# EEZ_PSU_power_board_r5B6c.net
KiCad netlist of a schematic drawn in EAGLE
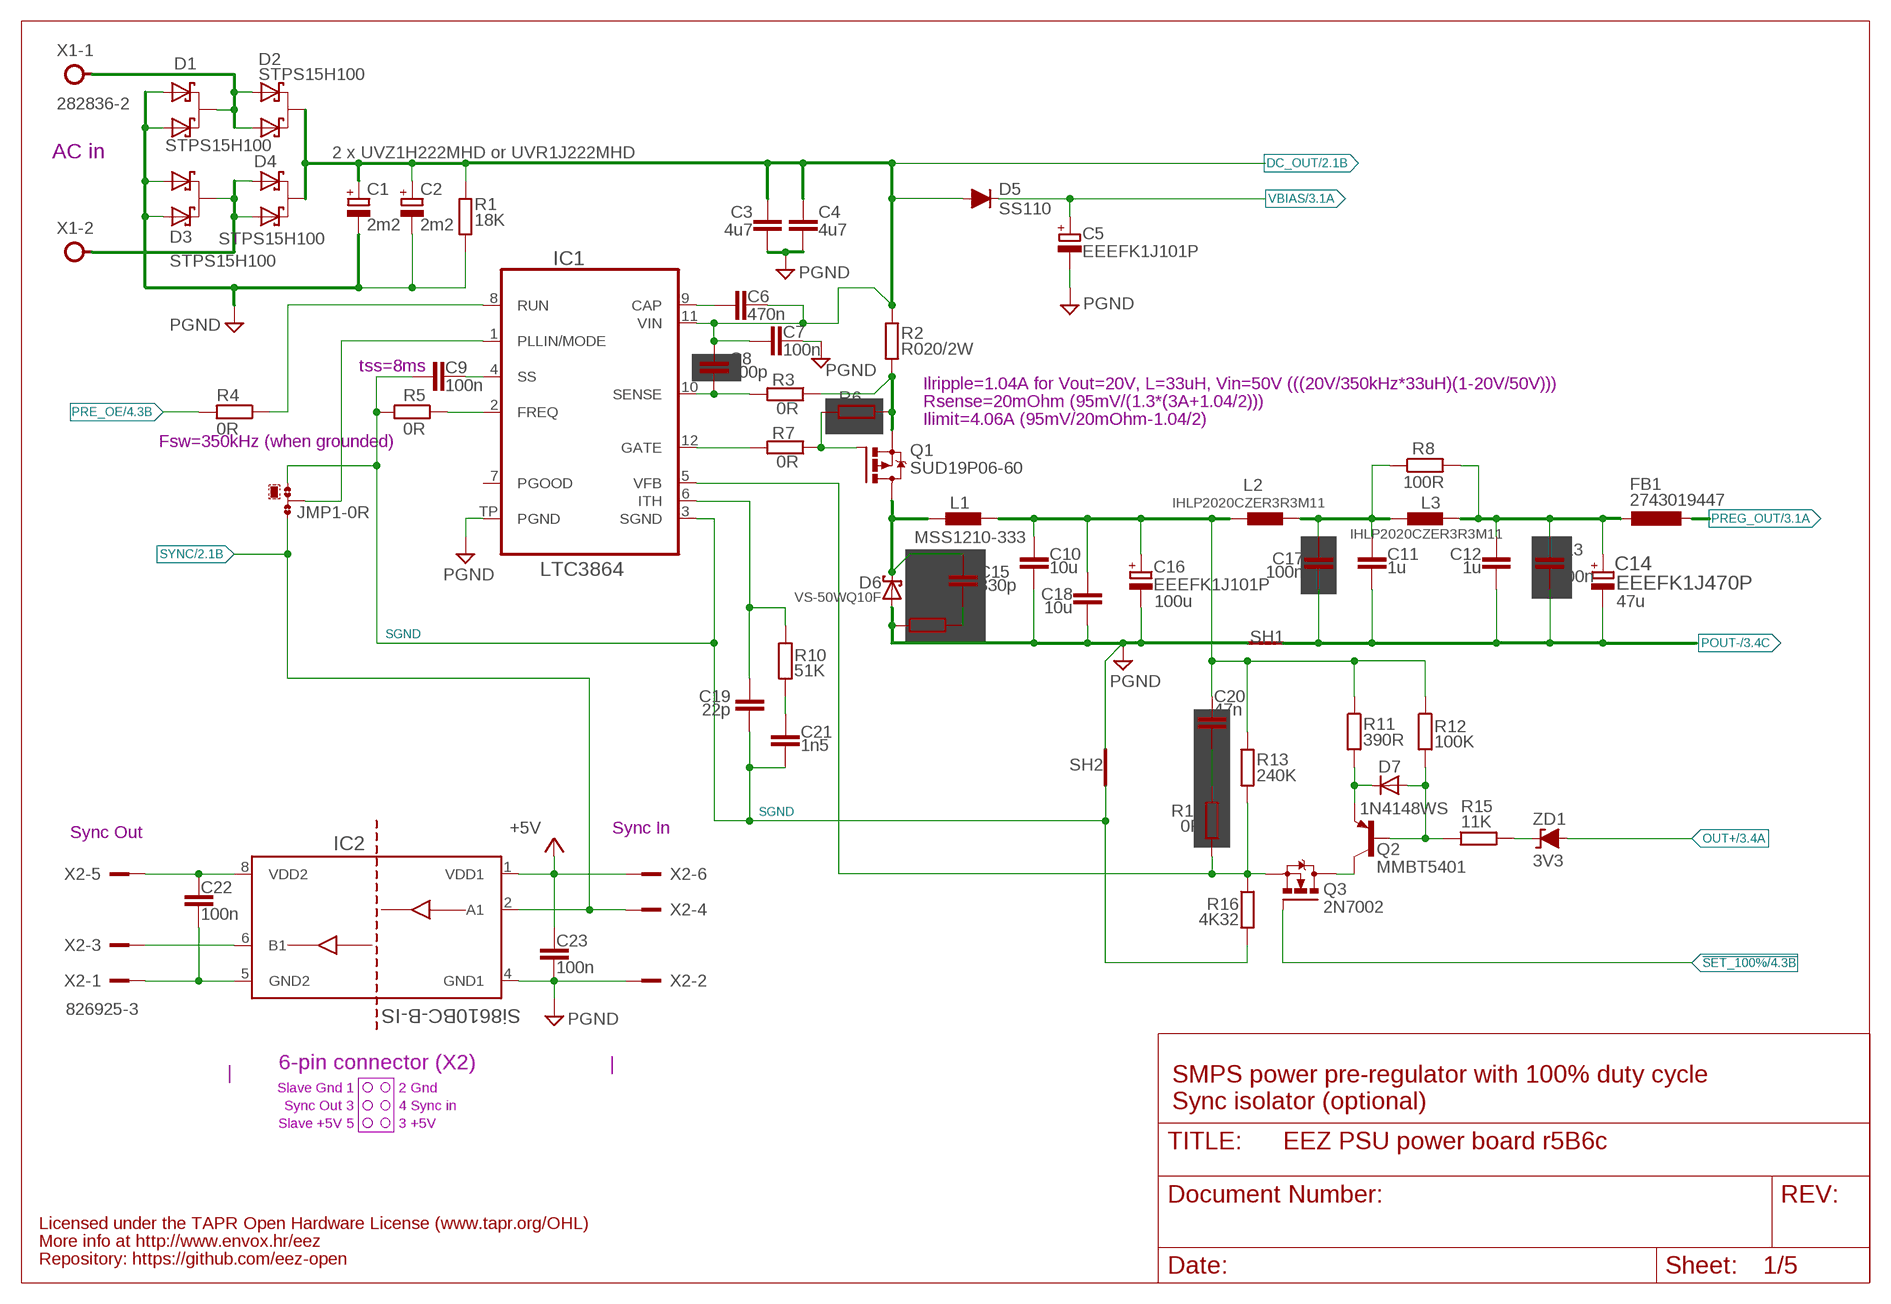
[diagram p0: schematic, sheet 1]
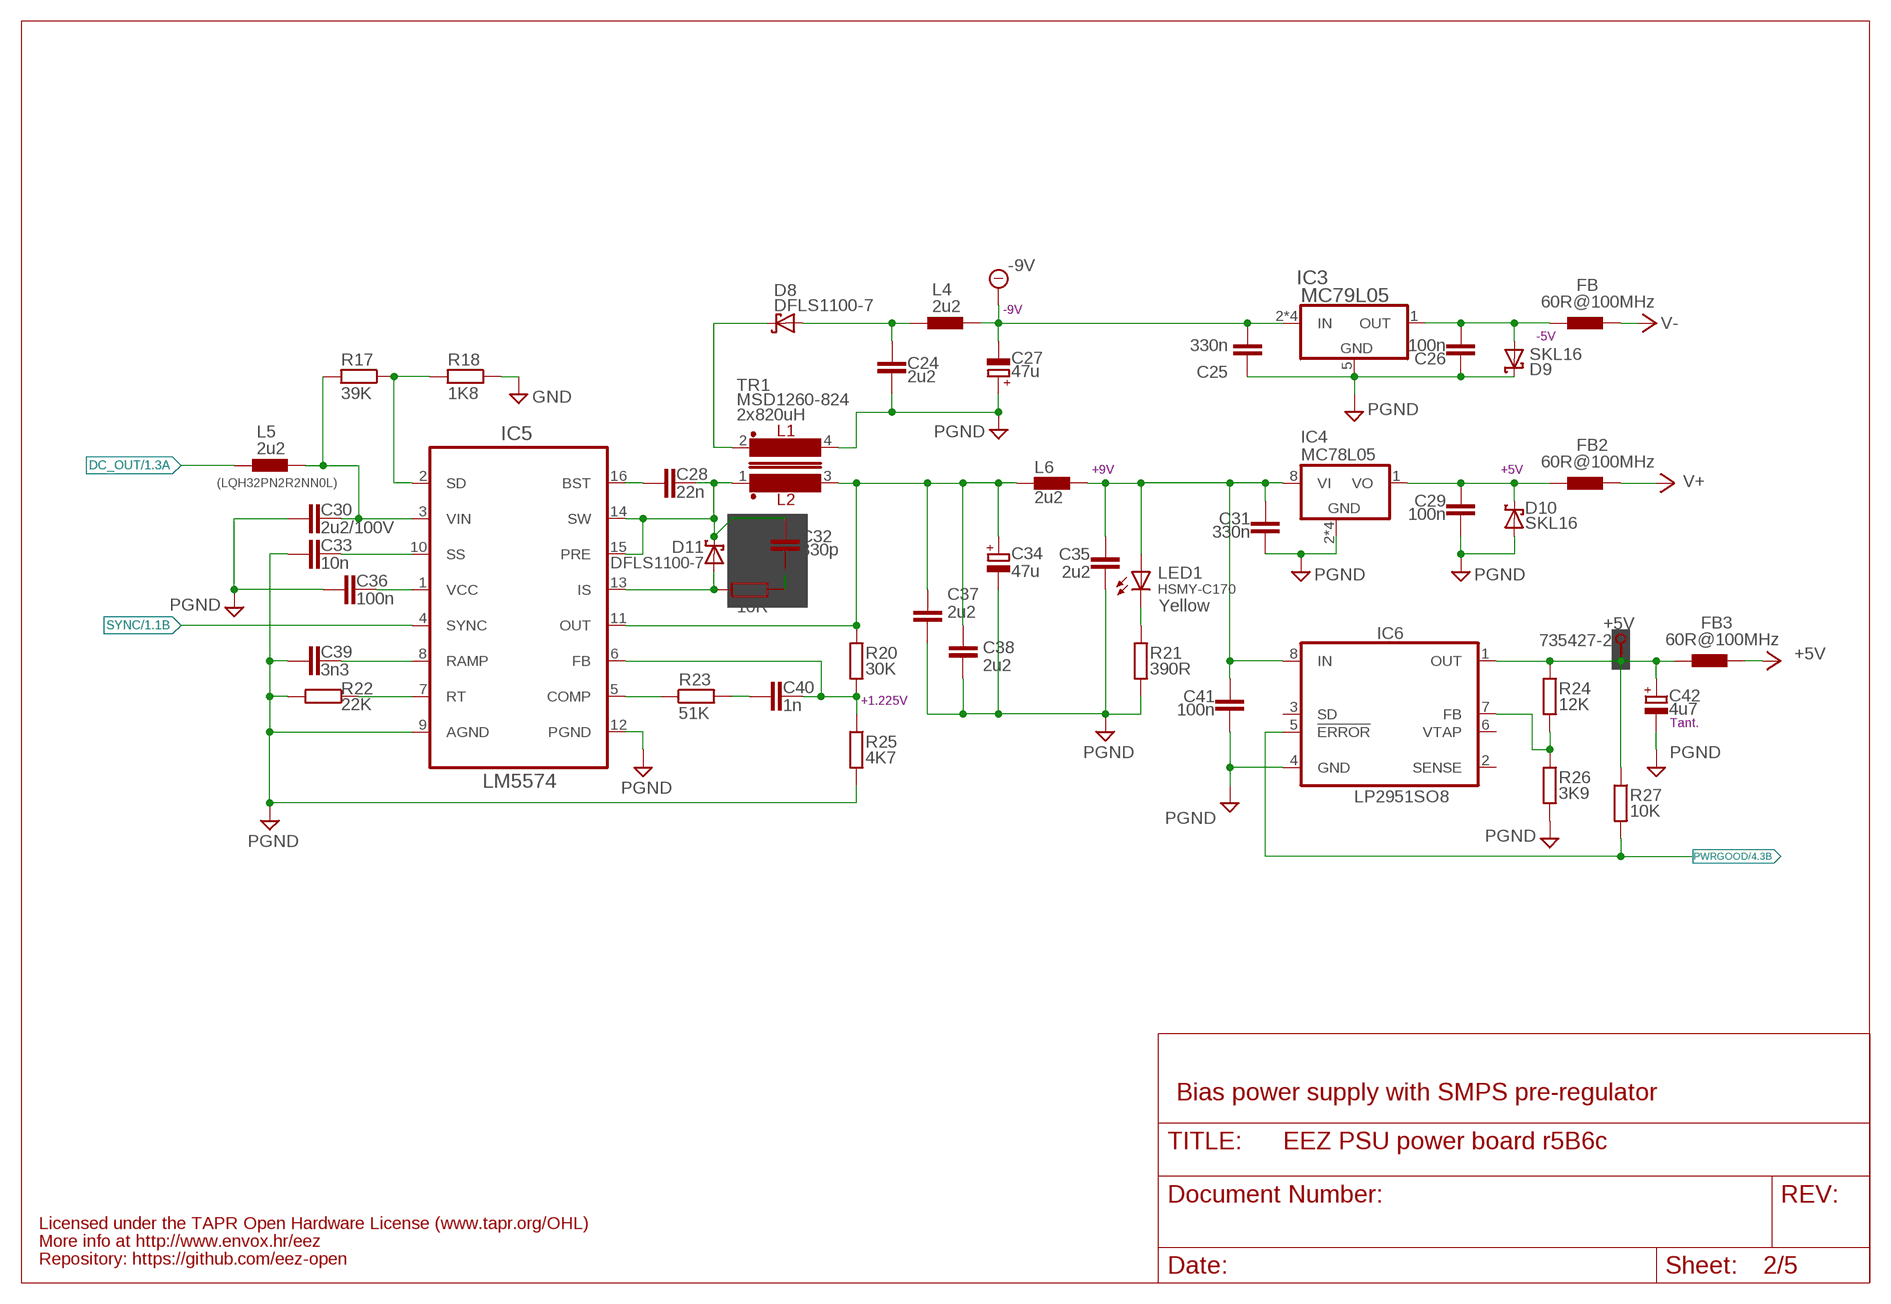
[diagram p1: schematic, sheet 2]
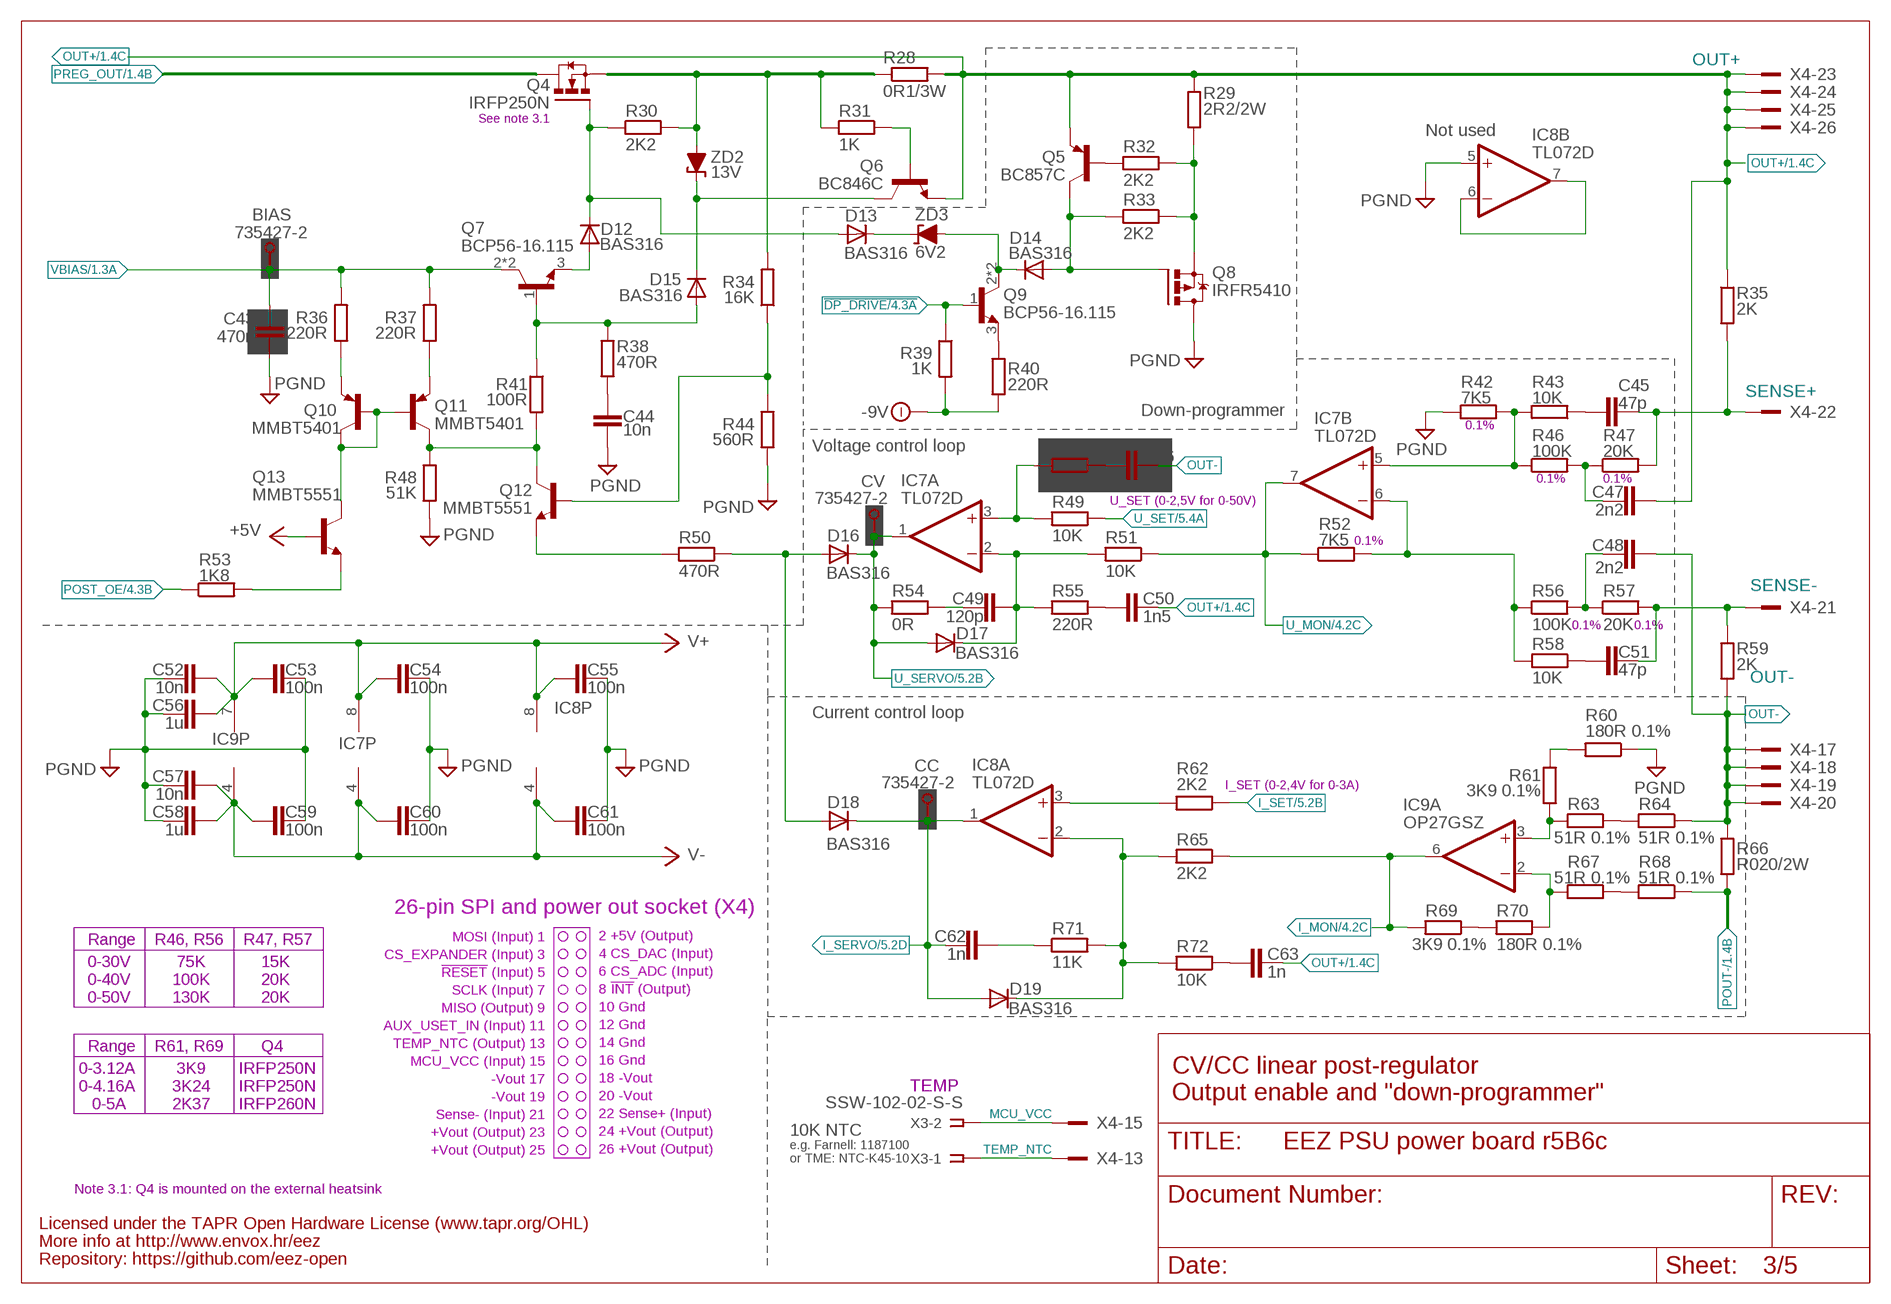
[diagram p2: schematic, sheet 3]
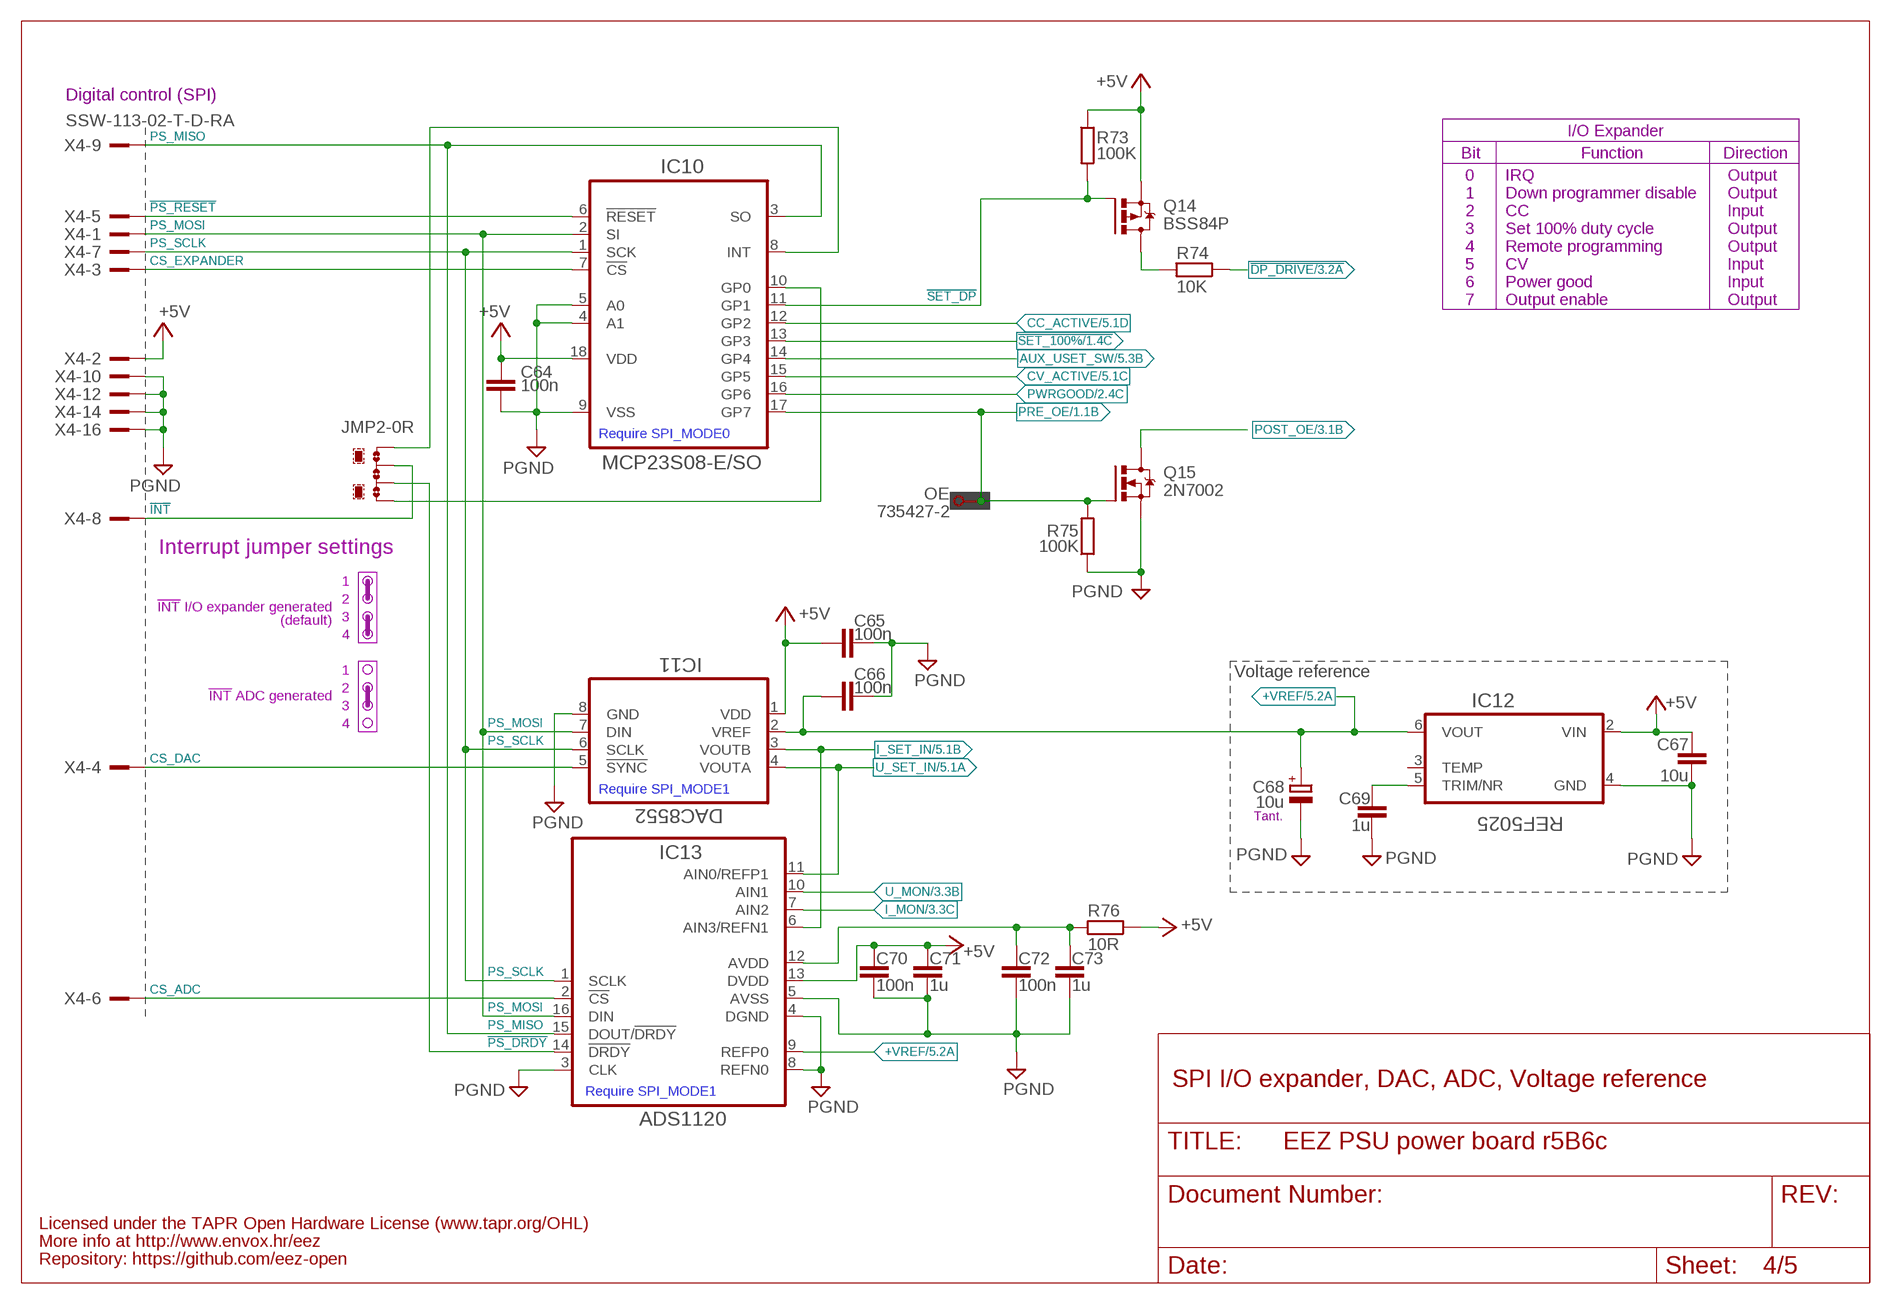
[diagram p3: schematic, sheet 4]
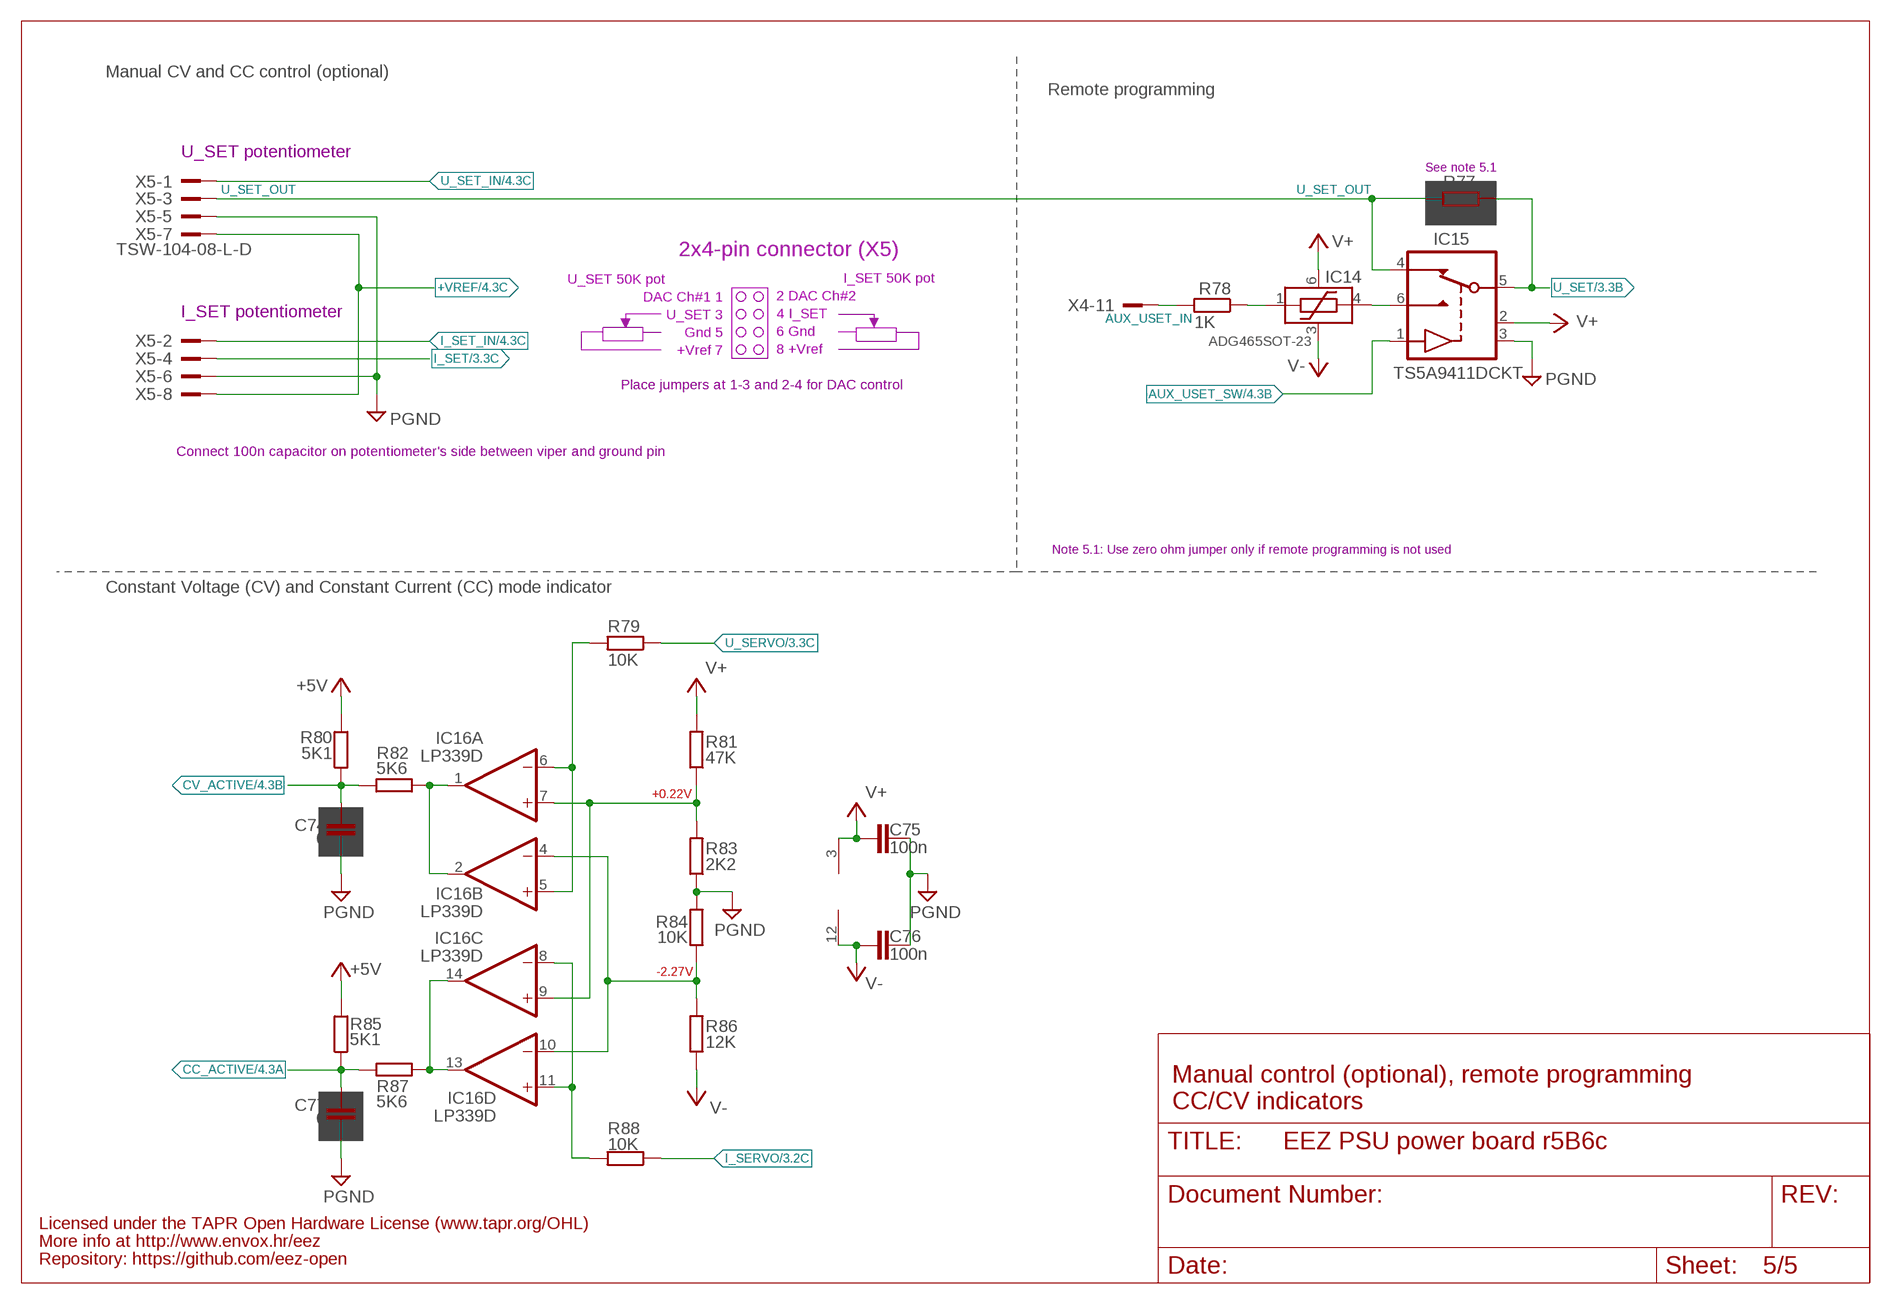
[diagram p4: schematic, sheet 5]

(export (version "E")
  (design (tool "Eeschema 10.0.6"))
  (components
    (comp (ref "C64")
      (value "100n")
      (footprint "eagle-import:C0603")
      (libsource (lib "eagle-import") (part "C-EUC0603"))
    )
    (comp (ref "C65")
      (value "100n")
      (footprint "eagle-import:C0603")
      (libsource (lib "eagle-import") (part "C-EUC0603"))
    )
    (comp (ref "C66")
      (value "100n")
      (footprint "eagle-import:C0603")
      (libsource (lib "eagle-import") (part "C-EUC0603"))
    )
    (comp (ref "C67")
      (value "10u")
      (footprint "eagle-import:C1206")
      (libsource (lib "eagle-import") (part "C-EUC1206"))
    )
    (comp (ref "C68")
      (value "10u")
      (footprint "eagle-import:EC1206")
      (libsource (lib "eagle-import") (part "ECAP1206"))
    )
    (comp (ref "C69")
      (value "1u")
      (footprint "eagle-import:C0805")
      (libsource (lib "eagle-import") (part "C-EUC0805"))
    )
    (comp (ref "C70")
      (value "100n")
      (footprint "eagle-import:C0603")
      (libsource (lib "eagle-import") (part "C-EUC0603"))
    )
    (comp (ref "C71")
      (value "1u")
      (footprint "eagle-import:C0805")
      (libsource (lib "eagle-import") (part "C-EUC0805"))
    )
    (comp (ref "C72")
      (value "100n")
      (footprint "eagle-import:C0603")
      (libsource (lib "eagle-import") (part "C-EUC0603"))
    )
    (comp (ref "C73")
      (value "1u")
      (footprint "eagle-import:C0805")
      (libsource (lib "eagle-import") (part "C-EUC0805"))
    )
    (comp (ref "IC10")
      (value "MCP23S08-E/SO")
      (footprint "eagle-import:SOIC127P1030X265-18N")
      (libsource (lib "eagle-import") (part "MCP23S08"))
    )
    (comp (ref "IC11")
      (value "DAC8552")
      (footprint "eagle-import:DGK8-M")
      (libsource (lib "eagle-import") (part "DAC8552_DGK_8M"))
    )
    (comp (ref "IC12")
      (value "REF5025")
      (footprint "eagle-import:SOIC127P600X175-8N")
      (libsource (lib "eagle-import") (part "REF50XX"))
    )
    (comp (ref "IC13")
      (value "ADS1120")
      (footprint "eagle-import:PW(R-PDSO-G16)")
      (libsource (lib "eagle-import") (part "ADS1120TSSOP-16"))
    )
    (comp (ref "JMP2")
      (value "0R-JMP41-2,3-4")
      (footprint "eagle-import:0R-JMP4")
      (libsource (lib "eagle-import") (part "0R-JMP41-2,3-4"))
    )
    (comp (ref "OE")
      (value "735427-2")
      (footprint "eagle-import:PCB_SHIELD_TAB")
      (libsource (lib "eagle-import") (part "PCB_TEST_TABSHIELD"))
    )
    (comp (ref "Q14")
      (value "BSS84P")
      (footprint "eagle-import:SOT95P237X112-3N")
      (fields (field (name "MPN") "IRLML2246TRPBF"))
      (libsource (lib "eagle-import") (part "IRLML2246TRPBF"))
    )
    (comp (ref "Q15")
      (value "2N7002")
      (footprint "eagle-import:SOT103P240X110-3N")
      (fields
        (field (name "MPN") "2N7002-7-F")
        (field (name "MPN_1") "2N7002-7-F")
        (field (name "OC_FARNELL") "1713823")
        (field (name "OC_NEWARK") "25R5679")
        (field (name "PACKAGE") "SOT-23-3")
        (field (name "SUPPLIER") "DIODES INC.")
      )
      (libsource (lib "eagle-import") (part "2N7002"))
    )
    (comp (ref "R73")
      (value "100K")
      (footprint "eagle-import:R0805")
      (libsource (lib "eagle-import") (part "R-EU_R0805"))
    )
    (comp (ref "R74")
      (value "10K")
      (footprint "eagle-import:R0805")
      (libsource (lib "eagle-import") (part "R-EU_R0805"))
    )
    (comp (ref "R75")
      (value "100K")
      (footprint "eagle-import:R0805")
      (libsource (lib "eagle-import") (part "R-EU_R0805"))
    )
    (comp (ref "R76")
      (value "10R")
      (footprint "eagle-import:R0805")
      (libsource (lib "eagle-import") (part "R-EU_R0805"))
    )
    (comp (ref "X4")
      (value "SSW-113-02-T-D-RA")
      (footprint "eagle-import:SSW-113-02-T-D-RA")
      (fields (field (name "FARNELL") "1805583"))
      (libsource (lib "eagle-import") (part "SSW-113-02-T-D-RA"))
    )
    (comp (ref "C74")
      (value "0")
      (footprint "eagle-import:C0603")
      (libsource (lib "eagle-import") (part "C-EUC0603"))
    )
    (comp (ref "C75")
      (value "100n")
      (footprint "eagle-import:C0603")
      (libsource (lib "eagle-import") (part "C-EUC0603"))
    )
    (comp (ref "C76")
      (value "100n")
      (footprint "eagle-import:C0603")
      (libsource (lib "eagle-import") (part "C-EUC0603"))
    )
    (comp (ref "C77")
      (value "0")
      (footprint "eagle-import:C0603")
      (libsource (lib "eagle-import") (part "C-EUC0603"))
    )
    (comp (ref "IC14")
      (value "ADG465SOT-23")
      (footprint "eagle-import:SOT95P280X145-6N")
      (libsource (lib "eagle-import") (part "ADG465SOT-23"))
    )
    (comp (ref "IC15")
      (value "TS5A9411DCKT")
      (footprint "eagle-import:SOT65P210X110-6N")
      (libsource (lib "eagle-import") (part "TS5A9411DCKT"))
    )
    (comp (ref "IC16")
      (value "LP339D")
      (footprint "eagle-import:SOIC127P600X175-14N")
      (libsource (lib "eagle-import") (part "LM339SO14"))
    )
    (comp (ref "R77")
      (value "0R")
      (footprint "eagle-import:R0805")
      (libsource (lib "eagle-import") (part "R-EU_R0805"))
    )
    (comp (ref "R78")
      (value "1K")
      (footprint "eagle-import:R0805")
      (libsource (lib "eagle-import") (part "R-EU_R0805"))
    )
    (comp (ref "R79")
      (value "10K")
      (footprint "eagle-import:R0805")
      (libsource (lib "eagle-import") (part "R-EU_R0805"))
    )
    (comp (ref "R80")
      (value "5K1")
      (footprint "eagle-import:R0805")
      (libsource (lib "eagle-import") (part "R-EU_R0805"))
    )
    (comp (ref "R81")
      (value "47K")
      (footprint "eagle-import:R0805")
      (libsource (lib "eagle-import") (part "R-EU_R0805"))
    )
    (comp (ref "R82")
      (value "5K6")
      (footprint "eagle-import:R0805")
      (libsource (lib "eagle-import") (part "R-EU_R0805"))
    )
    (comp (ref "R83")
      (value "2K2")
      (footprint "eagle-import:R0805")
      (libsource (lib "eagle-import") (part "R-EU_R0805"))
    )
    (comp (ref "R84")
      (value "10K")
      (footprint "eagle-import:R0805")
      (libsource (lib "eagle-import") (part "R-EU_R0805"))
    )
    (comp (ref "R85")
      (value "5K1")
      (footprint "eagle-import:R0805")
      (libsource (lib "eagle-import") (part "R-EU_R0805"))
    )
    (comp (ref "R86")
      (value "12K")
      (footprint "eagle-import:R0805")
      (libsource (lib "eagle-import") (part "R-EU_R0805"))
    )
    (comp (ref "R87")
      (value "5K6")
      (footprint "eagle-import:R0805")
      (libsource (lib "eagle-import") (part "R-EU_R0805"))
    )
    (comp (ref "R88")
      (value "10K")
      (footprint "eagle-import:R0805")
      (libsource (lib "eagle-import") (part "R-EU_R0805"))
    )
    (comp (ref "X5")
      (value "TSW-104-08-L-D")
      (footprint "eagle-import:TSW-104-02-S-D")
      (libsource (lib "eagle-import") (part "TSW-104-02-S-D"))
    )
    (comp (ref "+5V")
      (value "735427-2")
      (footprint "eagle-import:PCB_SHIELD_TAB")
      (libsource (lib "eagle-import") (part "PCB_TEST_TABSHIELD"))
    )
    (comp (ref "C24")
      (value "2u2")
      (footprint "eagle-import:C0805")
      (libsource (lib "eagle-import") (part "C-EUC0805"))
    )
    (comp (ref "C25")
      (value "330n")
      (footprint "eagle-import:C0805")
      (libsource (lib "eagle-import") (part "C-EUC0805"))
    )
    (comp (ref "C26")
      (value "100n")
      (footprint "eagle-import:C0805")
      (libsource (lib "eagle-import") (part "C-EUC0805"))
    )
    (comp (ref "C27")
      (value "47u")
      (footprint "eagle-import:CAPAE660X610N")
      (libsource (lib "eagle-import") (part "ECAPPANASONIC_H"))
    )
    (comp (ref "C28")
      (value "22n")
      (footprint "eagle-import:C0805")
      (libsource (lib "eagle-import") (part "C-EUC0805"))
    )
    (comp (ref "C29")
      (value "100n")
      (footprint "eagle-import:C0805")
      (libsource (lib "eagle-import") (part "C-EUC0805"))
    )
    (comp (ref "C30")
      (value "2u2/100V")
      (footprint "eagle-import:C1210")
      (libsource (lib "eagle-import") (part "C-EUC1210"))
    )
    (comp (ref "C31")
      (value "330n")
      (footprint "eagle-import:C0805")
      (libsource (lib "eagle-import") (part "C-EUC0805"))
    )
    (comp (ref "C32")
      (value "330p")
      (footprint "eagle-import:C0805")
      (libsource (lib "eagle-import") (part "C-EUC0805"))
    )
    (comp (ref "C33")
      (value "10n")
      (footprint "eagle-import:C0805")
      (libsource (lib "eagle-import") (part "C-EUC0805"))
    )
    (comp (ref "C34")
      (value "47u")
      (footprint "eagle-import:CAPAE660X610N")
      (libsource (lib "eagle-import") (part "ECAPPANASONIC_H"))
    )
    (comp (ref "C35")
      (value "2u2")
      (footprint "eagle-import:C0805")
      (libsource (lib "eagle-import") (part "C-EUC0805"))
    )
    (comp (ref "C36")
      (value "100n")
      (footprint "eagle-import:C0805")
      (libsource (lib "eagle-import") (part "C-EUC0805"))
    )
    (comp (ref "C37")
      (value "2u2")
      (footprint "eagle-import:C0805")
      (libsource (lib "eagle-import") (part "C-EUC0805"))
    )
    (comp (ref "C38")
      (value "2u2")
      (footprint "eagle-import:C0805")
      (libsource (lib "eagle-import") (part "C-EUC0805"))
    )
    (comp (ref "C39")
      (value "3n3")
      (footprint "eagle-import:C0805")
      (libsource (lib "eagle-import") (part "C-EUC0805"))
    )
    (comp (ref "C40")
      (value "1n")
      (footprint "eagle-import:C0805")
      (libsource (lib "eagle-import") (part "C-EUC0805"))
    )
    (comp (ref "C41")
      (value "100n")
      (footprint "eagle-import:C0805")
      (libsource (lib "eagle-import") (part "C-EUC0805"))
    )
    (comp (ref "C42")
      (value "4u7")
      (footprint "eagle-import:EC1206")
      (libsource (lib "eagle-import") (part "ECAP1206"))
    )
    (comp (ref "D8")
      (value "DFLS1100-7")
      (footprint "eagle-import:SOD123")
      (libsource (lib "eagle-import") (part "SCHOTTKYSOD123"))
    )
    (comp (ref "D9")
      (value "SKL16")
      (footprint "eagle-import:SOD123")
      (libsource (lib "eagle-import") (part "SCHOTTKYSOD123"))
    )
    (comp (ref "D10")
      (value "SKL16")
      (footprint "eagle-import:SOD123")
      (libsource (lib "eagle-import") (part "SCHOTTKYSOD123"))
    )
    (comp (ref "D11")
      (value "DFLS1100-7")
      (footprint "eagle-import:SOD123")
      (libsource (lib "eagle-import") (part "SCHOTTKYSOD123"))
    )
    (comp (ref "FB")
      (value "60R@100MHz")
      (footprint "eagle-import:BEAD0603")
      (libsource (lib "eagle-import") (part "FERRITE_BEAD0603"))
    )
    (comp (ref "FB2")
      (value "60R@100MHz")
      (footprint "eagle-import:BEAD0603")
      (libsource (lib "eagle-import") (part "FERRITE_BEAD0603"))
    )
    (comp (ref "FB3")
      (value "60R@100MHz")
      (footprint "eagle-import:BEAD0603")
      (libsource (lib "eagle-import") (part "FERRITE_BEAD0603"))
    )
    (comp (ref "IC3")
      (value "MC79L05")
      (footprint "eagle-import:SOIC127P600X173-8N")
      (libsource (lib "eagle-import") (part "MC79LXXSOIC"))
    )
    (comp (ref "IC4")
      (value "MC78L05")
      (footprint "eagle-import:SOIC127P600X173-8N")
      (libsource (lib "eagle-import") (part "MC78LXXSOIC8"))
    )
    (comp (ref "IC5")
      (value "LM5574")
      (footprint "eagle-import:SOP65P640X110-16N")
      (fields (field (name "MPN") "LM5574MT"))
      (libsource (lib "eagle-import") (part "LM5574"))
    )
    (comp (ref "IC6")
      (value "LP2951SO8")
      (footprint "eagle-import:SOIC127P600X175-8N")
      (libsource (lib "eagle-import") (part "LP2951SO8"))
    )
    (comp (ref "L4")
      (value "2u2")
      (footprint "eagle-import:L1210")
      (libsource (lib "eagle-import") (part "L1210"))
    )
    (comp (ref "L5")
      (value "2u2")
      (footprint "eagle-import:L1210")
      (libsource (lib "eagle-import") (part "L1210"))
    )
    (comp (ref "L6")
      (value "2u2")
      (footprint "eagle-import:L1210")
      (libsource (lib "eagle-import") (part "L1210"))
    )
    (comp (ref "LED1")
      (value "HSMY-C170")
      (footprint "eagle-import:CHIPLED_0805")
      (libsource (lib "eagle-import") (part "LEDCHIPLED_0805"))
    )
    (comp (ref "R17")
      (value "39K")
      (footprint "eagle-import:R0805")
      (libsource (lib "eagle-import") (part "R-EU_R0805"))
    )
    (comp (ref "R18")
      (value "1K8")
      (footprint "eagle-import:R0805")
      (libsource (lib "eagle-import") (part "R-EU_R0805"))
    )
    (comp (ref "R19")
      (value "10R")
      (footprint "eagle-import:R1206")
      (libsource (lib "eagle-import") (part "R-EU_R1206"))
    )
    (comp (ref "R20")
      (value "30K")
      (footprint "eagle-import:R0805")
      (libsource (lib "eagle-import") (part "R-EU_R0805"))
    )
    (comp (ref "R21")
      (value "390R")
      (footprint "eagle-import:R0805")
      (libsource (lib "eagle-import") (part "R-EU_R0805"))
    )
    (comp (ref "R22")
      (value "22K")
      (footprint "eagle-import:R0805")
      (libsource (lib "eagle-import") (part "R-EU_R0805"))
    )
    (comp (ref "R23")
      (value "51K")
      (footprint "eagle-import:R0805")
      (libsource (lib "eagle-import") (part "R-EU_R0805"))
    )
    (comp (ref "R24")
      (value "12K")
      (footprint "eagle-import:R0805")
      (libsource (lib "eagle-import") (part "R-EU_R0805"))
    )
    (comp (ref "R25")
      (value "4K7")
      (footprint "eagle-import:R0805")
      (libsource (lib "eagle-import") (part "R-EU_R0805"))
    )
    (comp (ref "R26")
      (value "3K9")
      (footprint "eagle-import:R0805")
      (libsource (lib "eagle-import") (part "R-EU_R0805"))
    )
    (comp (ref "R27")
      (value "10K")
      (footprint "eagle-import:R0805")
      (libsource (lib "eagle-import") (part "R-EU_R0805"))
    )
    (comp (ref "TR1")
      (value "MSD1260-824")
      (footprint "eagle-import:MSD1260")
      (libsource (lib "eagle-import") (part "COILCRAFT_MSD1260INV"))
    )
    (comp (ref "BIAS")
      (value "735427-2")
      (footprint "eagle-import:PCB_SHIELD_TAB")
      (libsource (lib "eagle-import") (part "PCB_TEST_TABSHIELD"))
    )
    (comp (ref "C43")
      (value "470n")
      (footprint "eagle-import:C1812")
      (libsource (lib "eagle-import") (part "C-EUC1812"))
    )
    (comp (ref "C44")
      (value "10n")
      (footprint "eagle-import:C0805")
      (libsource (lib "eagle-import") (part "C-EUC0805"))
    )
    (comp (ref "C45")
      (value "47p")
      (footprint "eagle-import:C0805")
      (libsource (lib "eagle-import") (part "C-EUC0805"))
    )
    (comp (ref "C46")
      (value "1n5")
      (footprint "eagle-import:C0805")
      (libsource (lib "eagle-import") (part "C-EUC0805"))
    )
    (comp (ref "C47")
      (value "2n2")
      (footprint "eagle-import:C0805")
      (libsource (lib "eagle-import") (part "C-EUC0805"))
    )
    (comp (ref "C48")
      (value "2n2")
      (footprint "eagle-import:C0805")
      (libsource (lib "eagle-import") (part "C-EUC0805"))
    )
    (comp (ref "C49")
      (value "120p")
      (footprint "eagle-import:C0805")
      (libsource (lib "eagle-import") (part "C-EUC0805"))
    )
    (comp (ref "C50")
      (value "1n5")
      (footprint "eagle-import:C0805")
      (libsource (lib "eagle-import") (part "C-EUC0805"))
    )
    (comp (ref "C51")
      (value "47p")
      (footprint "eagle-import:C0805")
      (libsource (lib "eagle-import") (part "C-EUC0805"))
    )
    (comp (ref "C52")
      (value "10n")
      (footprint "eagle-import:C0805")
      (libsource (lib "eagle-import") (part "C-EUC0805"))
    )
    (comp (ref "C53")
      (value "100n")
      (footprint "eagle-import:C0603")
      (libsource (lib "eagle-import") (part "C-EUC0603"))
    )
    (comp (ref "C54")
      (value "100n")
      (footprint "eagle-import:C0603")
      (libsource (lib "eagle-import") (part "C-EUC0603"))
    )
    (comp (ref "C55")
      (value "100n")
      (footprint "eagle-import:C0603")
      (libsource (lib "eagle-import") (part "C-EUC0603"))
    )
    (comp (ref "C56")
      (value "1u")
      (footprint "eagle-import:C0805")
      (libsource (lib "eagle-import") (part "C-EUC0805"))
    )
    (comp (ref "C57")
      (value "10n")
      (footprint "eagle-import:C0805")
      (libsource (lib "eagle-import") (part "C-EUC0805"))
    )
    (comp (ref "C58")
      (value "1u")
      (footprint "eagle-import:C0805")
      (libsource (lib "eagle-import") (part "C-EUC0805"))
    )
    (comp (ref "C59")
      (value "100n")
      (footprint "eagle-import:C0603")
      (libsource (lib "eagle-import") (part "C-EUC0603"))
    )
    (comp (ref "C60")
      (value "100n")
      (footprint "eagle-import:C0603")
      (libsource (lib "eagle-import") (part "C-EUC0603"))
    )
    (comp (ref "C61")
      (value "100n")
      (footprint "eagle-import:C0603")
      (libsource (lib "eagle-import") (part "C-EUC0603"))
    )
    (comp (ref "C62")
      (value "1n")
      (footprint "eagle-import:C0805")
      (libsource (lib "eagle-import") (part "C-EUC0805"))
    )
    (comp (ref "C63")
      (value "1n")
      (footprint "eagle-import:C0805")
      (libsource (lib "eagle-import") (part "C-EUC0805"))
    )
    (comp (ref "CC")
      (value "735427-2")
      (footprint "eagle-import:PCB_SHIELD_TAB")
      (libsource (lib "eagle-import") (part "PCB_TEST_TABSHIELD"))
    )
    (comp (ref "CV")
      (value "735427-2")
      (footprint "eagle-import:PCB_SHIELD_TAB")
      (libsource (lib "eagle-import") (part "PCB_TEST_TABSHIELD"))
    )
    (comp (ref "D12")
      (value "BAS316")
      (footprint "eagle-import:SOD323-W")
      (libsource (lib "eagle-import") (part "DIODE-SOD323-W"))
    )
    (comp (ref "D13")
      (value "BAS316")
      (footprint "eagle-import:SOD323-W")
      (libsource (lib "eagle-import") (part "DIODE-SOD323-W"))
    )
    (comp (ref "D14")
      (value "BAS316")
      (footprint "eagle-import:SOD323-W")
      (libsource (lib "eagle-import") (part "DIODE-SOD323-W"))
    )
    (comp (ref "D15")
      (value "BAS316")
      (footprint "eagle-import:SOD323-W")
      (libsource (lib "eagle-import") (part "DIODE-SOD323-W"))
    )
    (comp (ref "D16")
      (value "BAS316")
      (footprint "eagle-import:SOD323-W")
      (libsource (lib "eagle-import") (part "DIODE-SOD323-W"))
    )
    (comp (ref "D17")
      (value "BAS316")
      (footprint "eagle-import:SOD323-W")
      (libsource (lib "eagle-import") (part "DIODE-SOD323-W"))
    )
    (comp (ref "D18")
      (value "BAS316")
      (footprint "eagle-import:SOD323-W")
      (libsource (lib "eagle-import") (part "DIODE-SOD323-W"))
    )
    (comp (ref "D19")
      (value "BAS316")
      (footprint "eagle-import:SOD323-W")
      (libsource (lib "eagle-import") (part "DIODE-SOD323-W"))
    )
    (comp (ref "IC7")
      (value "TL072D")
      (footprint "eagle-import:SOIC127P600X173-8N")
      (libsource (lib "eagle-import") (part "TL072SOIC8"))
    )
    (comp (ref "IC8")
      (value "TL072D")
      (footprint "eagle-import:SOIC127P600X173-8N")
      (libsource (lib "eagle-import") (part "TL072SOIC8"))
    )
    (comp (ref "IC9")
      (value "OP27GSZ")
      (footprint "eagle-import:SOIC127P600X173-8N")
      (libsource (lib "eagle-import") (part "OP27GSZSO8"))
    )
    (comp (ref "Q4")
      (value "IRFP250N")
      (footprint "eagle-import:TO247BH-CLR")
      (libsource (lib "eagle-import") (part "IRFP240BOTTOM"))
    )
    (comp (ref "Q5")
      (value "BC857C")
      (footprint "eagle-import:SOT23-BEC")
      (libsource (lib "eagle-import") (part "-PNP-SOT23-BECBC857C"))
    )
    (comp (ref "Q6")
      (value "BC846C")
      (footprint "eagle-import:SOT23-BEC")
      (libsource (lib "eagle-import") (part "-NPN-SOT23-BECBC846B"))
    )
    (comp (ref "Q7")
      (value "BCP56-16.115")
      (footprint "eagle-import:SOT230P700X180-4N")
      (libsource (lib "eagle-import") (part "BCP56"))
    )
    (comp (ref "Q8")
      (value "IRFR5410")
      (footprint "eagle-import:TO229P990X239-3N")
      (libsource (lib "eagle-import") (part "P-MOSFETDPAK"))
    )
    (comp (ref "Q9")
      (value "BCP56-16.115")
      (footprint "eagle-import:SOT230P700X180-4N")
      (libsource (lib "eagle-import") (part "BCP56"))
    )
    (comp (ref "Q10")
      (value "MMBT5401")
      (footprint "eagle-import:SOT23-BEC")
      (libsource (lib "eagle-import") (part "-PNP-SOT23-BECBC857B"))
    )
    (comp (ref "Q11")
      (value "MMBT5401")
      (footprint "eagle-import:SOT23-BEC")
      (libsource (lib "eagle-import") (part "-PNP-SOT23-BECBC857B"))
    )
    (comp (ref "Q12")
      (value "MMBT5551")
      (footprint "eagle-import:SOT23-BEC")
      (libsource (lib "eagle-import") (part "-NPN-SOT23-BECMMBT5551LT1"))
    )
    (comp (ref "Q13")
      (value "MMBT5551")
      (footprint "eagle-import:SOT23-BEC")
      (libsource (lib "eagle-import") (part "-NPN-SOT23-BECMMBT5551LT1"))
    )
    (comp (ref "R28")
      (value "0R1/3W")
      (footprint "eagle-import:R_2512+0411_15")
      (libsource (lib "eagle-import") (part "R_EUCOMBO"))
    )
    (comp (ref "R29")
      (value "2R2/2W")
      (footprint "eagle-import:R_2512+0411_15")
      (libsource (lib "eagle-import") (part "R_EUCOMBO"))
    )
    (comp (ref "R30")
      (value "2K2")
      (footprint "eagle-import:R0805")
      (libsource (lib "eagle-import") (part "R-EU_R0805"))
    )
    (comp (ref "R31")
      (value "1K")
      (footprint "eagle-import:R0805")
      (libsource (lib "eagle-import") (part "R-EU_R0805"))
    )
    (comp (ref "R32")
      (value "2K2")
      (footprint "eagle-import:R0805")
      (libsource (lib "eagle-import") (part "R-EU_R0805"))
    )
    (comp (ref "R33")
      (value "2K2")
      (footprint "eagle-import:R0805")
      (libsource (lib "eagle-import") (part "R-EU_R0805"))
    )
    (comp (ref "R34")
      (value "16K")
      (footprint "eagle-import:R0805")
      (libsource (lib "eagle-import") (part "R-EU_R0805"))
    )
    (comp (ref "R35")
      (value "2K")
      (footprint "eagle-import:R0805")
      (libsource (lib "eagle-import") (part "R-EU_R0805"))
    )
    (comp (ref "R36")
      (value "220R")
      (footprint "eagle-import:R0805")
      (libsource (lib "eagle-import") (part "R-EU_R0805"))
    )
    (comp (ref "R37")
      (value "220R")
      (footprint "eagle-import:R0805")
      (libsource (lib "eagle-import") (part "R-EU_R0805"))
    )
    (comp (ref "R38")
      (value "470R")
      (footprint "eagle-import:R0805")
      (libsource (lib "eagle-import") (part "R-EU_R0805"))
    )
    (comp (ref "R39")
      (value "1K")
      (footprint "eagle-import:R0805")
      (libsource (lib "eagle-import") (part "R-EU_R0805"))
    )
    (comp (ref "R40")
      (value "220R")
      (footprint "eagle-import:R0805")
      (libsource (lib "eagle-import") (part "R-EU_R0805"))
    )
    (comp (ref "R41")
      (value "100R")
      (footprint "eagle-import:R0805")
      (libsource (lib "eagle-import") (part "R-EU_R0805"))
    )
    (comp (ref "R42")
      (value "7K5")
      (footprint "eagle-import:R0805")
      (libsource (lib "eagle-import") (part "R-EU_R0805"))
    )
    (comp (ref "R43")
      (value "10K")
      (footprint "eagle-import:R0805")
      (libsource (lib "eagle-import") (part "R-EU_R0805"))
    )
    (comp (ref "R44")
      (value "560R")
      (footprint "eagle-import:R0805")
      (libsource (lib "eagle-import") (part "R-EU_R0805"))
    )
    (comp (ref "R45")
      (value "220R")
      (footprint "eagle-import:R0805")
      (libsource (lib "eagle-import") (part "R-EU_R0805"))
    )
    (comp (ref "R46")
      (value "100K")
      (footprint "eagle-import:R0805")
      (libsource (lib "eagle-import") (part "R-EU_R0805"))
    )
    (comp (ref "R47")
      (value "20K")
      (footprint "eagle-import:R0805")
      (libsource (lib "eagle-import") (part "R-EU_R0805"))
    )
    (comp (ref "R48")
      (value "51K")
      (footprint "eagle-import:R0805")
      (libsource (lib "eagle-import") (part "R-EU_R0805"))
    )
    (comp (ref "R49")
      (value "10K")
      (footprint "eagle-import:R0805")
      (libsource (lib "eagle-import") (part "R-EU_R0805"))
    )
    (comp (ref "R50")
      (value "470R")
      (footprint "eagle-import:R0805")
      (libsource (lib "eagle-import") (part "R-EU_R0805"))
    )
    (comp (ref "R51")
      (value "10K")
      (footprint "eagle-import:R0805")
      (libsource (lib "eagle-import") (part "R-EU_R0805"))
    )
    (comp (ref "R52")
      (value "7K5")
      (footprint "eagle-import:R0805")
      (libsource (lib "eagle-import") (part "R-EU_R0805"))
    )
    (comp (ref "R53")
      (value "1K8")
      (footprint "eagle-import:R0805")
      (libsource (lib "eagle-import") (part "R-EU_R0805"))
    )
    (comp (ref "R54")
      (value "0R")
      (footprint "eagle-import:R0805")
      (libsource (lib "eagle-import") (part "R-EU_R0805"))
    )
    (comp (ref "R55")
      (value "220R")
      (footprint "eagle-import:R0805")
      (libsource (lib "eagle-import") (part "R-EU_R0805"))
    )
    (comp (ref "R56")
      (value "100K")
      (footprint "eagle-import:R0805")
      (libsource (lib "eagle-import") (part "R-EU_R0805"))
    )
    (comp (ref "R57")
      (value "20K")
      (footprint "eagle-import:R0805")
      (libsource (lib "eagle-import") (part "R-EU_R0805"))
    )
    (comp (ref "R58")
      (value "10K")
      (footprint "eagle-import:R0805")
      (libsource (lib "eagle-import") (part "R-EU_R0805"))
    )
    (comp (ref "R59")
      (value "2K")
      (footprint "eagle-import:R0805")
      (libsource (lib "eagle-import") (part "R-EU_R0805"))
    )
    (comp (ref "R60")
      (value "180R 0.1%")
      (footprint "eagle-import:R0805")
      (libsource (lib "eagle-import") (part "R-EU_R0805"))
    )
    (comp (ref "R61")
      (value "3K9 0.1%")
      (footprint "eagle-import:R0805")
      (libsource (lib "eagle-import") (part "R-EU_R0805"))
    )
    (comp (ref "R62")
      (value "2K2")
      (footprint "eagle-import:R0805")
      (libsource (lib "eagle-import") (part "R-EU_R0805"))
    )
    (comp (ref "R63")
      (value "51R 0.1%")
      (footprint "eagle-import:R0805")
      (libsource (lib "eagle-import") (part "R-EU_R0805"))
    )
    (comp (ref "R64")
      (value "51R 0.1%")
      (footprint "eagle-import:R0805")
      (libsource (lib "eagle-import") (part "R-EU_R0805"))
    )
    (comp (ref "R65")
      (value "2K2")
      (footprint "eagle-import:R0805")
      (libsource (lib "eagle-import") (part "R-EU_R0805"))
    )
    (comp (ref "R66")
      (value "R020/2W")
      (footprint "eagle-import:R2512")
      (libsource (lib "eagle-import") (part "R-EU_R2512"))
    )
    (comp (ref "R67")
      (value "51R 0.1%")
      (footprint "eagle-import:R0805")
      (libsource (lib "eagle-import") (part "R-EU_R0805"))
    )
    (comp (ref "R68")
      (value "51R 0.1%")
      (footprint "eagle-import:R0805")
      (libsource (lib "eagle-import") (part "R-EU_R0805"))
    )
    (comp (ref "R69")
      (value "3K9 0.1%")
      (footprint "eagle-import:R0805")
      (libsource (lib "eagle-import") (part "R-EU_R0805"))
    )
    (comp (ref "R70")
      (value "180R 0.1%")
      (footprint "eagle-import:R0805")
      (libsource (lib "eagle-import") (part "R-EU_R0805"))
    )
    (comp (ref "R71")
      (value "11K")
      (footprint "eagle-import:R0805")
      (libsource (lib "eagle-import") (part "R-EU_R0805"))
    )
    (comp (ref "R72")
      (value "10K")
      (footprint "eagle-import:R0805")
      (libsource (lib "eagle-import") (part "R-EU_R0805"))
    )
    (comp (ref "X3")
      (value "SSW-102-02-S-S")
      (footprint "eagle-import:SSW-102-02-S-S")
      (libsource (lib "eagle-import") (part "SSW-102-02-S-S"))
    )
    (comp (ref "ZD2")
      (value "13V")
      (footprint "eagle-import:MINIMELF")
      (libsource (lib "eagle-import") (part "ZENER-DIODEMINIMELF"))
    )
    (comp (ref "ZD3")
      (value "6V2")
      (footprint "eagle-import:MINIMELF")
      (libsource (lib "eagle-import") (part "ZENER-DIODEMINIMELF"))
    )
    (comp (ref "C1")
      (value "2m2")
      (footprint "eagle-import:ECAP7.5_18")
      (libsource (lib "eagle-import") (part "ECAP7.5G_18MM"))
    )
    (comp (ref "C2")
      (value "2m2")
      (footprint "eagle-import:ECAP7.5_18")
      (libsource (lib "eagle-import") (part "ECAP7.5G_18MM"))
    )
    (comp (ref "C3")
      (value "4u7")
      (footprint "eagle-import:C1210")
      (libsource (lib "eagle-import") (part "C-EUC1210"))
    )
    (comp (ref "C4")
      (value "4u7")
      (footprint "eagle-import:C1210")
      (libsource (lib "eagle-import") (part "C-EUC1210"))
    )
    (comp (ref "C5")
      (value "EEEFK1J101P")
      (footprint "eagle-import:ECAP5_10.5+PANASONIC_F")
      (libsource (lib "eagle-import") (part "ECAP5G_10.5MM_F"))
    )
    (comp (ref "C6")
      (value "470n")
      (footprint "eagle-import:C0805")
      (libsource (lib "eagle-import") (part "C-EUC0805"))
    )
    (comp (ref "C7")
      (value "100n")
      (footprint "eagle-import:C0805")
      (libsource (lib "eagle-import") (part "C-EUC0805"))
    )
    (comp (ref "C8")
      (value "100p")
      (footprint "eagle-import:C0805")
      (libsource (lib "eagle-import") (part "C-EUC0805"))
    )
    (comp (ref "C9")
      (value "100n")
      (footprint "eagle-import:C0805")
      (libsource (lib "eagle-import") (part "C-EUC0805"))
    )
    (comp (ref "C10")
      (value "10u")
      (footprint "eagle-import:C1210")
      (libsource (lib "eagle-import") (part "C-EUC1210"))
    )
    (comp (ref "C11")
      (value "1u")
      (footprint "eagle-import:C1206")
      (libsource (lib "eagle-import") (part "resistor_C-EUC1206"))
    )
    (comp (ref "C12")
      (value "1u")
      (footprint "eagle-import:C1206")
      (libsource (lib "eagle-import") (part "resistor_C-EUC1206"))
    )
    (comp (ref "C13")
      (value "100n")
      (footprint "eagle-import:C0805")
      (libsource (lib "eagle-import") (part "C-EUC0805"))
    )
    (comp (ref "C14")
      (value "EEEFK1J470P")
      (footprint "eagle-import:CAPAE830X1050N")
      (fields (field (name "MPN") "EEE-FK1J470P") (field (name "TOLERANCE") "±20 %"))
      (libsource (lib "eagle-import") (part "EEE--CASE-FFK1J470P"))
    )
    (comp (ref "C15")
      (value "330p")
      (footprint "eagle-import:C0805")
      (libsource (lib "eagle-import") (part "C-EUC0805"))
    )
    (comp (ref "C16")
      (value "EEEFK1J101P")
      (footprint "eagle-import:ECAP5_10.5+PANASONIC_F")
      (libsource (lib "eagle-import") (part "ECAP5G_10.5MM_F"))
    )
    (comp (ref "C17")
      (value "100n")
      (footprint "eagle-import:C0805")
      (libsource (lib "eagle-import") (part "C-EUC0805"))
    )
    (comp (ref "C18")
      (value "10u")
      (footprint "eagle-import:C1210")
      (libsource (lib "eagle-import") (part "C-EUC1210"))
    )
    (comp (ref "C19")
      (value "22p")
      (footprint "eagle-import:C0805")
      (libsource (lib "eagle-import") (part "C-EUC0805"))
    )
    (comp (ref "C20")
      (value "47n")
      (footprint "eagle-import:C0805")
      (libsource (lib "eagle-import") (part "C-EUC0805"))
    )
    (comp (ref "C21")
      (value "1n5")
      (footprint "eagle-import:C0805")
      (libsource (lib "eagle-import") (part "C-EUC0805"))
    )
    (comp (ref "C22")
      (value "100n")
      (footprint "eagle-import:C0603")
      (libsource (lib "eagle-import") (part "C-EUC0603"))
    )
    (comp (ref "C23")
      (value "100n")
      (footprint "eagle-import:C0603")
      (libsource (lib "eagle-import") (part "C-EUC0603"))
    )
    (comp (ref "D1")
      (value "STPS15H100")
      (footprint "eagle-import:TO252@1")
      (libsource (lib "eagle-import") (part "VS-6CWQ06FNPBF"))
    )
    (comp (ref "D2")
      (value "STPS15H100")
      (footprint "eagle-import:TO252@1")
      (libsource (lib "eagle-import") (part "VS-6CWQ06FNPBF"))
    )
    (comp (ref "D3")
      (value "STPS15H100")
      (footprint "eagle-import:TO252@1")
      (libsource (lib "eagle-import") (part "VS-6CWQ06FNPBF"))
    )
    (comp (ref "D4")
      (value "STPS15H100")
      (footprint "eagle-import:TO252@1")
      (libsource (lib "eagle-import") (part "VS-6CWQ06FNPBF"))
    )
    (comp (ref "D5")
      (value "SS110")
      (footprint "eagle-import:DO214AA")
      (libsource (lib "eagle-import") (part "DIODEDO214AA"))
    )
    (comp (ref "D6")
      (value "VS-50WQ10F")
      (footprint "eagle-import:TO252@1")
      (libsource (lib "eagle-import") (part "SCHOTTKYTO252"))
    )
    (comp (ref "D7")
      (value "1N4148WS")
      (footprint "eagle-import:SOD323-W")
      (libsource (lib "eagle-import") (part "DIODE-SOD323-W"))
    )
    (comp (ref "FB1")
      (value "2743019447")
      (footprint "eagle-import:L1812")
      (libsource (lib "eagle-import") (part "L-EUL1812"))
    )
    (comp (ref "IC1")
      (value "LTC3864")
      (footprint "eagle-import:LTC_05-08-1666")
      (libsource (lib "eagle-import") (part "LTC3864"))
    )
    (comp (ref "IC2")
      (value "Si8610BC-B-IS")
      (footprint "eagle-import:SOIC127P600X173-8N")
      (libsource (lib "eagle-import") (part "SI8610"))
    )
    (comp (ref "JMP1")
      (value "0R-JUMPA")
      (footprint "eagle-import:A0R-JMP")
      (libsource (lib "eagle-import") (part "0R-JUMPA"))
    )
    (comp (ref "L1")
      (value "MSS1210-333")
      (footprint "eagle-import:MSS1210")
      (libsource (lib "eagle-import") (part "COILCRAFT_MSS1210"))
    )
    (comp (ref "L2")
      (value "IHLP2020CZER3R3M11")
      (footprint "eagle-import:IHLP-2020BZ-11")
      (libsource (lib "eagle-import") (part "IHLP-2020BZ-11"))
    )
    (comp (ref "L3")
      (value "IHLP2020CZER3R3M11")
      (footprint "eagle-import:IHLP-2020BZ-11")
      (libsource (lib "eagle-import") (part "IHLP-2020BZ-11"))
    )
    (comp (ref "Q1")
      (value "SUD19P06-60")
      (footprint "eagle-import:TO229P990X239-3N")
      (libsource (lib "eagle-import") (part "P-MOSFETDPAK"))
    )
    (comp (ref "Q2")
      (value "MMBT5401")
      (footprint "eagle-import:SOT23-BEC")
      (libsource (lib "eagle-import") (part "-PNP-SOT23-BECBC857B"))
    )
    (comp (ref "Q3")
      (value "2N7002")
      (footprint "eagle-import:SOT103P240X110-3N")
      (fields (field (name "MPN") "2N7002-7-F"))
      (libsource (lib "eagle-import") (part "2N7002"))
    )
    (comp (ref "R1")
      (value "18K")
      (footprint "eagle-import:R1206")
      (libsource (lib "eagle-import") (part "R-EU_R1206"))
    )
    (comp (ref "R2")
      (value "R020/2W")
      (footprint "eagle-import:R2512")
      (libsource (lib "eagle-import") (part "R-EU_R2512"))
    )
    (comp (ref "R3")
      (value "0R")
      (footprint "eagle-import:R0805")
      (libsource (lib "eagle-import") (part "R-EU_R0805"))
    )
    (comp (ref "R4")
      (value "0R")
      (footprint "eagle-import:R0805")
      (libsource (lib "eagle-import") (part "R-EU_R0805"))
    )
    (comp (ref "R5")
      (value "0R")
      (footprint "eagle-import:R0805")
      (libsource (lib "eagle-import") (part "R-EU_R0805"))
    )
    (comp (ref "R6")
      (value "100K")
      (footprint "eagle-import:R0805")
      (libsource (lib "eagle-import") (part "R-EU_R0805"))
    )
    (comp (ref "R7")
      (value "0R")
      (footprint "eagle-import:R0805")
      (libsource (lib "eagle-import") (part "R-EU_R0805"))
    )
    (comp (ref "R8")
      (value "100R")
      (footprint "eagle-import:R0805")
      (libsource (lib "eagle-import") (part "R-EU_R0805"))
    )
    (comp (ref "R9")
      (value "10R")
      (footprint "eagle-import:R1206")
      (libsource (lib "eagle-import") (part "R-EU_R1206"))
    )
    (comp (ref "R10")
      (value "51K")
      (footprint "eagle-import:R0805")
      (libsource (lib "eagle-import") (part "R-EU_R0805"))
    )
    (comp (ref "R11")
      (value "390R")
      (footprint "eagle-import:R0805")
      (libsource (lib "eagle-import") (part "R-EU_R0805"))
    )
    (comp (ref "R12")
      (value "100K")
      (footprint "eagle-import:R0805")
      (libsource (lib "eagle-import") (part "R-EU_R0805"))
    )
    (comp (ref "R13")
      (value "240K")
      (footprint "eagle-import:R0805")
      (libsource (lib "eagle-import") (part "R-EU_R0805"))
    )
    (comp (ref "R14")
      (value "0R")
      (footprint "eagle-import:R0805")
      (libsource (lib "eagle-import") (part "R-EU_R0805"))
    )
    (comp (ref "R15")
      (value "11K")
      (footprint "eagle-import:R0805")
      (libsource (lib "eagle-import") (part "R-EU_R0805"))
    )
    (comp (ref "R16")
      (value "4K32")
      (footprint "eagle-import:R0805")
      (libsource (lib "eagle-import") (part "R-EU_R0805"))
    )
    (comp (ref "SH1")
      (value "Pgnd to Pout- short")
      (footprint "eagle-import:SHORT_NOHOLE")
      (libsource (lib "eagle-import") (part "SHORTNOHOLE"))
    )
    (comp (ref "SH2")
      (value "Sgnd to Pgnd short")
      (footprint "eagle-import:SHORT_NOHOLE")
      (libsource (lib "eagle-import") (part "SHORTNOHOLE"))
    )
    (comp (ref "X1")
      (value "282836-2")
      (footprint "eagle-import:TBLOCK5.0_2")
      (libsource (lib "eagle-import") (part "TBLOCK5.0_2A"))
    )
    (comp (ref "X2")
      (value "826925-3")
      (footprint "eagle-import:TSW-103-07-F-D")
      (libsource (lib "eagle-import") (part "TSW-103-07-F-D"))
    )
    (comp (ref "ZD1")
      (value "3V3")
      (footprint "eagle-import:MINIMELF")
      (libsource (lib "eagle-import") (part "ZENER-DIODEMINIMELF"))
    )
  )
  (nets
    (net (code "1") (name "+5V") (class "Default")
      (node (ref "C23") (pin "1") (pinfunction "1_1") (pintype "passive"))
      (node (ref "C64") (pin "1") (pinfunction "1_1") (pintype "passive"))
      (node (ref "C65") (pin "2") (pinfunction "2_2") (pintype "passive"))
      (node (ref "C67") (pin "1") (pinfunction "1_1") (pintype "passive"))
      (node (ref "C70") (pin "2") (pinfunction "2_2") (pintype "passive"))
      (node (ref "C71") (pin "2") (pinfunction "2_2") (pintype "passive"))
      (node (ref "FB3") (pin "P$2") (pinfunction "2_P$2") (pintype "passive"))
      (node (ref "IC10") (pin "18") (pinfunction "VDD_18") (pintype "power_in"))
      (node (ref "IC11") (pin "1") (pinfunction "VDD_1") (pintype "power_in"))
      (node (ref "IC12") (pin "2") (pinfunction "VIN_2") (pintype "passive"))
      (node (ref "IC13") (pin "13") (pinfunction "DVDD_13") (pintype "power_in"))
      (node (ref "IC2") (pin "1") (pinfunction "VDD1_1") (pintype "power_in"))
      (node (ref "Q13") (pin "B") (pinfunction "B_B") (pintype "passive"))
      (node (ref "Q14") (pin "2") (pinfunction "S_2") (pintype "passive"))
      (node (ref "R73") (pin "1") (pinfunction "1_1") (pintype "passive"))
      (node (ref "R76") (pin "1") (pinfunction "1_1") (pintype "passive"))
      (node (ref "R80") (pin "2") (pinfunction "2_2") (pintype "passive"))
      (node (ref "R85") (pin "2") (pinfunction "2_2") (pintype "passive"))
      (node (ref "X2") (pin "6") (pinfunction "1_6") (pintype "passive"))
      (node (ref "X4") (pin "2") (pinfunction "1_2") (pintype "passive"))
    )
    (net (code "2") (name "+VREF") (class "Default")
      (node (ref "C66") (pin "2") (pinfunction "2_2") (pintype "passive"))
      (node (ref "C68") (pin "+") (pinfunction "+_+") (pintype "passive"))
      (node (ref "IC11") (pin "2") (pinfunction "VREF_2") (pintype "input"))
      (node (ref "IC12") (pin "6") (pinfunction "VOUT_6") (pintype "output"))
      (node (ref "IC13") (pin "9") (pinfunction "REFP0_9") (pintype "input"))
      (node (ref "X5") (pin "7") (pinfunction "1_7") (pintype "passive"))
      (node (ref "X5") (pin "8") (pinfunction "1_8") (pintype "passive"))
    )
    (net (code "3") (name "-9V") (class "Default")
      (node (ref "C25") (pin "2") (pinfunction "2_2") (pintype "passive"))
      (node (ref "C27") (pin "2") (pinfunction "-_2") (pintype "passive"))
      (node (ref "IC3") (pin "2") (pinfunction "IN_2") (pintype "input"))
      (node (ref "IC3") (pin "3") (pinfunction "IN_3") (pintype "input"))
      (node (ref "IC3") (pin "6") (pinfunction "IN_6") (pintype "input"))
      (node (ref "IC3") (pin "7") (pinfunction "IN_7") (pintype "input"))
      (node (ref "L4") (pin "2") (pinfunction "2_2") (pintype "passive"))
      (node (ref "R39") (pin "2") (pinfunction "2_2") (pintype "passive"))
      (node (ref "R40") (pin "2") (pinfunction "2_2") (pintype "passive"))
    )
    (net (code "4") (name "AUX_USET_IN") (class "Default")
      (node (ref "R78") (pin "2") (pinfunction "2_2") (pintype "passive"))
      (node (ref "X4") (pin "11") (pinfunction "1_11") (pintype "passive"))
    )
    (net (code "5") (name "AUX_USET_SW") (class "Default")
      (node (ref "IC10") (pin "14") (pinfunction "GP4_14") (pintype "bidirectional"))
      (node (ref "IC15") (pin "1") (pinfunction "IN_1") (pintype "input"))
    )
    (net (code "6") (name "CC_ACTIVE") (class "Default")
      (node (ref "C77") (pin "1") (pinfunction "1_1") (pintype "passive"))
      (node (ref "IC10") (pin "12") (pinfunction "GP2_12") (pintype "bidirectional"))
      (node (ref "R85") (pin "1") (pinfunction "1_1") (pintype "passive"))
      (node (ref "R87") (pin "2") (pinfunction "2_2") (pintype "passive"))
    )
    (net (code "7") (name "CS_ADC") (class "Default")
      (node (ref "IC13") (pin "2") (pinfunction "~{CS}_2") (pintype "input"))
      (node (ref "X4") (pin "6") (pinfunction "1_6") (pintype "passive"))
    )
    (net (code "8") (name "CS_DAC") (class "Default")
      (node (ref "IC11") (pin "5") (pinfunction "~{SYNC}_5") (pintype "input"))
      (node (ref "X4") (pin "4") (pinfunction "1_4") (pintype "passive"))
    )
    (net (code "9") (name "CS_EXPANDER") (class "Default")
      (node (ref "IC10") (pin "7") (pinfunction "~{CS}_7") (pintype "input"))
      (node (ref "X4") (pin "3") (pinfunction "1_3") (pintype "passive"))
    )
    (net (code "10") (name "CV_ACTIVE") (class "Default")
      (node (ref "C74") (pin "1") (pinfunction "1_1") (pintype "passive"))
      (node (ref "IC10") (pin "15") (pinfunction "GP5_15") (pintype "bidirectional"))
      (node (ref "R80") (pin "1") (pinfunction "1_1") (pintype "passive"))
      (node (ref "R82") (pin "2") (pinfunction "2_2") (pintype "passive"))
    )
    (net (code "11") (name "DC_OUT") (class "Default")
      (node (ref "C1") (pin "+") (pinfunction "+_+") (pintype "passive"))
      (node (ref "C2") (pin "+") (pinfunction "+_+") (pintype "passive"))
      (node (ref "C3") (pin "1") (pinfunction "1_1") (pintype "passive"))
      (node (ref "C4") (pin "1") (pinfunction "1_1") (pintype "passive"))
      (node (ref "C6") (pin "2") (pinfunction "2_2") (pintype "passive"))
      (node (ref "C7") (pin "1") (pinfunction "1_1") (pintype "passive"))
      (node (ref "C8") (pin "1") (pinfunction "1_1") (pintype "passive"))
      (node (ref "D2") (pin "3") (pinfunction "C_3") (pintype "passive"))
      (node (ref "D4") (pin "3") (pinfunction "C_3") (pintype "passive"))
      (node (ref "D5") (pin "A") (pinfunction "A_A") (pintype "passive"))
      (node (ref "IC1") (pin "11") (pinfunction "VIN_11") (pintype "passive"))
      (node (ref "L5") (pin "1") (pinfunction "1_1") (pintype "passive"))
      (node (ref "R1") (pin "1") (pinfunction "1_1") (pintype "passive"))
      (node (ref "R2") (pin "1") (pinfunction "1_1") (pintype "passive"))
    )
    (net (code "12") (name "GND") (class "Default")
      (node (ref "C1") (pin "-") (pinfunction "-_-") (pintype "passive"))
      (node (ref "C10") (pin "2") (pinfunction "2_2") (pintype "passive"))
      (node (ref "C16") (pin "-") (pinfunction "-_-") (pintype "passive"))
      (node (ref "C16") (pin "-.1") (pinfunction "-_-.1") (pintype "passive"))
      (node (ref "C18") (pin "2") (pinfunction "2_2") (pintype "passive"))
      (node (ref "C2") (pin "-") (pinfunction "-_-") (pintype "passive"))
      (node (ref "C23") (pin "2") (pinfunction "2_2") (pintype "passive"))
      (node (ref "C24") (pin "2") (pinfunction "2_2") (pintype "passive"))
      (node (ref "C25") (pin "1") (pinfunction "1_1") (pintype "passive"))
      (node (ref "C26") (pin "1") (pinfunction "1_1") (pintype "passive"))
      (node (ref "C27") (pin "1") (pinfunction "+_1") (pintype "passive"))
      (node (ref "C29") (pin "2") (pinfunction "2_2") (pintype "passive"))
      (node (ref "C3") (pin "2") (pinfunction "2_2") (pintype "passive"))
      (node (ref "C30") (pin "2") (pinfunction "2_2") (pintype "passive"))
      (node (ref "C31") (pin "2") (pinfunction "2_2") (pintype "passive"))
      (node (ref "C33") (pin "2") (pinfunction "2_2") (pintype "passive"))
      (node (ref "C34") (pin "2") (pinfunction "-_2") (pintype "passive"))
      (node (ref "C35") (pin "2") (pinfunction "2_2") (pintype "passive"))
      (node (ref "C36") (pin "1") (pinfunction "1_1") (pintype "passive"))
      (node (ref "C37") (pin "2") (pinfunction "2_2") (pintype "passive"))
      (node (ref "C38") (pin "2") (pinfunction "2_2") (pintype "passive"))
      (node (ref "C39") (pin "1") (pinfunction "1_1") (pintype "passive"))
      (node (ref "C4") (pin "2") (pinfunction "2_2") (pintype "passive"))
      (node (ref "C41") (pin "2") (pinfunction "2_2") (pintype "passive"))
      (node (ref "C42") (pin "-") (pinfunction "-_-") (pintype "passive"))
      (node (ref "C43") (pin "2") (pinfunction "2_2") (pintype "passive"))
      (node (ref "C44") (pin "2") (pinfunction "2_2") (pintype "passive"))
      (node (ref "C5") (pin "-") (pinfunction "-_-") (pintype "passive"))
      (node (ref "C5") (pin "-.1") (pinfunction "-_-.1") (pintype "passive"))
      (node (ref "C52") (pin "1") (pinfunction "1_1") (pintype "passive"))
      (node (ref "C53") (pin "2") (pinfunction "2_2") (pintype "passive"))
      (node (ref "C54") (pin "1") (pinfunction "1_1") (pintype "passive"))
      (node (ref "C55") (pin "1") (pinfunction "1_1") (pintype "passive"))
      (node (ref "C56") (pin "1") (pinfunction "1_1") (pintype "passive"))
      (node (ref "C57") (pin "1") (pinfunction "1_1") (pintype "passive"))
      (node (ref "C58") (pin "1") (pinfunction "1_1") (pintype "passive"))
      (node (ref "C59") (pin "2") (pinfunction "2_2") (pintype "passive"))
      (node (ref "C60") (pin "1") (pinfunction "1_1") (pintype "passive"))
      (node (ref "C61") (pin "1") (pinfunction "1_1") (pintype "passive"))
      (node (ref "C64") (pin "2") (pinfunction "2_2") (pintype "passive"))
      (node (ref "C65") (pin "1") (pinfunction "1_1") (pintype "passive"))
      (node (ref "C66") (pin "1") (pinfunction "1_1") (pintype "passive"))
      (node (ref "C67") (pin "2") (pinfunction "2_2") (pintype "passive"))
      (node (ref "C68") (pin "-") (pinfunction "-_-") (pintype "passive"))
      (node (ref "C69") (pin "2") (pinfunction "2_2") (pintype "passive"))
      (node (ref "C7") (pin "2") (pinfunction "2_2") (pintype "passive"))
      (node (ref "C70") (pin "1") (pinfunction "1_1") (pintype "passive"))
      (node (ref "C71") (pin "1") (pinfunction "1_1") (pintype "passive"))
      (node (ref "C72") (pin "1") (pinfunction "1_1") (pintype "passive"))
      (node (ref "C73") (pin "1") (pinfunction "1_1") (pintype "passive"))
      (node (ref "C74") (pin "2") (pinfunction "2_2") (pintype "passive"))
      (node (ref "C75") (pin "1") (pinfunction "1_1") (pintype "passive"))
      (node (ref "C76") (pin "1") (pinfunction "1_1") (pintype "passive"))
      (node (ref "C77") (pin "2") (pinfunction "2_2") (pintype "passive"))
      (node (ref "D1") (pin "1") (pinfunction "A1_1") (pintype "passive"))
      (node (ref "D1") (pin "2") (pinfunction "A2_2") (pintype "passive"))
      (node (ref "D10") (pin "A") (pinfunction "A_A") (pintype "passive"))
      (node (ref "D3") (pin "1") (pinfunction "A1_1") (pintype "passive"))
      (node (ref "D3") (pin "2") (pinfunction "A2_2") (pintype "passive"))
      (node (ref "D6") (pin "1") (pinfunction "A_1") (pintype "passive"))
      (node (ref "D6") (pin "2") (pinfunction "A_2") (pintype "passive"))
      (node (ref "D9") (pin "C") (pinfunction "C_C") (pintype "passive"))
      (node (ref "IC1") (pin "TP") (pinfunction "PGND_TP") (pintype "passive"))
      (node (ref "IC10") (pin "4") (pinfunction "A1_4") (pintype "input"))
      (node (ref "IC10") (pin "5") (pinfunction "A0_5") (pintype "input"))
      (node (ref "IC10") (pin "9") (pinfunction "VSS_9") (pintype "power_in"))
      (node (ref "IC11") (pin "8") (pinfunction "GND_8") (pintype "power_in"))
      (node (ref "IC12") (pin "4") (pinfunction "GND_4") (pintype "passive"))
      (node (ref "IC13") (pin "3") (pinfunction "CLK_3") (pintype "bidirectional"))
      (node (ref "IC13") (pin "4") (pinfunction "DGND_4") (pintype "power_in"))
      (node (ref "IC13") (pin "5") (pinfunction "AVSS_5") (pintype "power_in"))
      (node (ref "IC13") (pin "8") (pinfunction "REFN0_8") (pintype "input"))
      (node (ref "IC15") (pin "3") (pinfunction "GND_3") (pintype "passive"))
      (node (ref "IC2") (pin "4") (pinfunction "GND1_4") (pintype "power_in"))
      (node (ref "IC3") (pin "5") (pinfunction "GND_5") (pintype "passive"))
      (node (ref "IC4") (pin "2") (pinfunction "GND_2") (pintype "passive"))
      (node (ref "IC4") (pin "3") (pinfunction "GND_3") (pintype "passive"))
      (node (ref "IC4") (pin "6") (pinfunction "GND_6") (pintype "passive"))
      (node (ref "IC4") (pin "7") (pinfunction "GND_7") (pintype "passive"))
      (node (ref "IC5") (pin "12") (pinfunction "PGND_12") (pintype "passive"))
      (node (ref "IC5") (pin "9") (pinfunction "AGND_9") (pintype "passive"))
      (node (ref "IC6") (pin "4") (pinfunction "GND_4") (pintype "passive"))
      (node (ref "IC8") (pin "5") (pinfunction "+IN_5") (pintype "input"))
      (node (ref "Q15") (pin "2") (pinfunction "S_2") (pintype "passive"))
      (node (ref "Q8") (pin "2") (pinfunction "D_2") (pintype "passive"))
      (node (ref "R1") (pin "2") (pinfunction "2_2") (pintype "passive"))
      (node (ref "R18") (pin "1") (pinfunction "1_1") (pintype "passive"))
      (node (ref "R21") (pin "2") (pinfunction "2_2") (pintype "passive"))
      (node (ref "R22") (pin "2") (pinfunction "2_2") (pintype "passive"))
      (node (ref "R25") (pin "2") (pinfunction "2_2") (pintype "passive"))
      (node (ref "R26") (pin "2") (pinfunction "2_2") (pintype "passive"))
      (node (ref "R42") (pin "1") (pinfunction "1_1") (pintype "passive"))
      (node (ref "R44") (pin "1") (pinfunction "1_1") (pintype "passive"))
      (node (ref "R48") (pin "1") (pinfunction "1_1") (pintype "passive"))
      (node (ref "R60") (pin "1") (pinfunction "1_1") (pintype "passive"))
      (node (ref "R75") (pin "1") (pinfunction "1_1") (pintype "passive"))
      (node (ref "R83") (pin "1") (pinfunction "1_1") (pintype "passive"))
      (node (ref "R84") (pin "2") (pinfunction "2_2") (pintype "passive"))
      (node (ref "R9") (pin "1") (pinfunction "1_1") (pintype "passive"))
      (node (ref "SH1") (pin "P$2") (pinfunction "GND_B_P$2") (pintype "bidirectional"))
      (node (ref "SH2") (pin "P$2") (pinfunction "GND_B_P$2") (pintype "bidirectional"))
      (node (ref "TR1") (pin "4") (pinfunction "4_4") (pintype "passive"))
      (node (ref "X2") (pin "2") (pinfunction "1_2") (pintype "passive"))
      (node (ref "X4") (pin "10") (pinfunction "1_10") (pintype "passive"))
      (node (ref "X4") (pin "12") (pinfunction "1_12") (pintype "passive"))
      (node (ref "X4") (pin "14") (pinfunction "1_14") (pintype "passive"))
      (node (ref "X4") (pin "16") (pinfunction "1_16") (pintype "passive"))
      (node (ref "X5") (pin "5") (pinfunction "1_5") (pintype "passive"))
      (node (ref "X5") (pin "6") (pinfunction "1_6") (pintype "passive"))
    )
    (net (code "13") (name "I_MON") (class "Default")
      (node (ref "IC13") (pin "7") (pinfunction "AIN2_7") (pintype "input"))
      (node (ref "IC9") (pin "6") (pinfunction "OUT_6") (pintype "output"))
      (node (ref "R65") (pin "1") (pinfunction "1_1") (pintype "passive"))
      (node (ref "R69") (pin "2") (pinfunction "2_2") (pintype "passive"))
    )
    (net (code "14") (name "I_SERVO") (class "Default")
      (node (ref "C62") (pin "2") (pinfunction "2_2") (pintype "passive"))
      (node (ref "CC") (pin "1") (pinfunction "P$1_1") (pintype "bidirectional"))
      (node (ref "D18") (pin "C") (pinfunction "C_C") (pintype "passive"))
      (node (ref "D19") (pin "A") (pinfunction "A_A") (pintype "passive"))
      (node (ref "IC8") (pin "1") (pinfunction "OUT_1") (pintype "output"))
      (node (ref "R88") (pin "1") (pinfunction "1_1") (pintype "passive"))
    )
    (net (code "15") (name "I_SET") (class "Default")
      (node (ref "R62") (pin "1") (pinfunction "1_1") (pintype "passive"))
      (node (ref "X5") (pin "4") (pinfunction "1_4") (pintype "passive"))
    )
    (net (code "16") (name "I_SET_IN") (class "Default")
      (node (ref "IC11") (pin "3") (pinfunction "VOUTB_3") (pintype "output"))
      (node (ref "IC13") (pin "6") (pinfunction "AIN3/REFN1_6") (pintype "input"))
      (node (ref "X5") (pin "2") (pinfunction "1_2") (pintype "passive"))
    )
    (net (code "17") (name "MCU_VCC") (class "Default")
      (node (ref "X3") (pin "2") (pinfunction "1_2") (pintype "passive"))
      (node (ref "X4") (pin "15") (pinfunction "1_15") (pintype "passive"))
    )
    (net (code "18") (name "Net-(+5V-P$1)") (class "Default")
      (node (ref "+5V") (pin "1") (pinfunction "P$1_1") (pintype "bidirectional"))
      (node (ref "C42") (pin "+") (pinfunction "+_+") (pintype "passive"))
      (node (ref "FB3") (pin "P$1") (pinfunction "1_P$1") (pintype "passive"))
      (node (ref "IC6") (pin "1") (pinfunction "OUT_1") (pintype "output"))
      (node (ref "R24") (pin "1") (pinfunction "1_1") (pintype "passive"))
      (node (ref "R27") (pin "1") (pinfunction "1_1") (pintype "passive"))
    )
    (net (code "19") (name "Net-(C10-Pad1)") (class "Default")
      (node (ref "C10") (pin "1") (pinfunction "1_1") (pintype "passive"))
      (node (ref "C16") (pin "+") (pinfunction "+_+") (pintype "passive"))
      (node (ref "C16") (pin "+.1") (pinfunction "+_+.1") (pintype "passive"))
      (node (ref "C18") (pin "1") (pinfunction "1_1") (pintype "passive"))
      (node (ref "C20") (pin "1") (pinfunction "1_1") (pintype "passive"))
      (node (ref "L1") (pin "2") (pinfunction "2_2") (pintype "passive"))
      (node (ref "L2") (pin "1") (pinfunction "1_1") (pintype "passive"))
      (node (ref "R11") (pin "1") (pinfunction "1_1") (pintype "passive"))
      (node (ref "R12") (pin "1") (pinfunction "1_1") (pintype "passive"))
      (node (ref "R13") (pin "1") (pinfunction "1_1") (pintype "passive"))
    )
    (net (code "20") (name "Net-(C11-Pad1)") (class "Default")
      (node (ref "C11") (pin "1") (pinfunction "1_1") (pintype "passive"))
      (node (ref "C17") (pin "2") (pinfunction "2_2") (pintype "passive"))
      (node (ref "L2") (pin "2") (pinfunction "2_2") (pintype "passive"))
      (node (ref "L3") (pin "1") (pinfunction "1_1") (pintype "passive"))
      (node (ref "R8") (pin "1") (pinfunction "1_1") (pintype "passive"))
    )
    (net (code "21") (name "Net-(C12-Pad1)") (class "Default")
      (node (ref "C12") (pin "1") (pinfunction "1_1") (pintype "passive"))
      (node (ref "C13") (pin "1") (pinfunction "1_1") (pintype "passive"))
      (node (ref "C14") (pin "1") (pinfunction "1_1") (pintype "passive"))
      (node (ref "FB1") (pin "1") (pinfunction "1_1") (pintype "passive"))
      (node (ref "L3") (pin "2") (pinfunction "2_2") (pintype "passive"))
      (node (ref "R8") (pin "2") (pinfunction "2_2") (pintype "passive"))
    )
    (net (code "22") (name "Net-(C15-Pad2)") (class "Default")
      (node (ref "C15") (pin "2") (pinfunction "2_2") (pintype "passive"))
      (node (ref "R9") (pin "2") (pinfunction "2_2") (pintype "passive"))
    )
    (net (code "23") (name "Net-(C20-Pad2)") (class "Default")
      (node (ref "C20") (pin "2") (pinfunction "2_2") (pintype "passive"))
      (node (ref "R14") (pin "2") (pinfunction "2_2") (pintype "passive"))
    )
    (net (code "24") (name "Net-(C21-Pad1)") (class "Default")
      (node (ref "C21") (pin "1") (pinfunction "1_1") (pintype "passive"))
      (node (ref "R10") (pin "1") (pinfunction "1_1") (pintype "passive"))
    )
    (net (code "25") (name "Net-(C24-Pad1)") (class "Default")
      (node (ref "C24") (pin "1") (pinfunction "1_1") (pintype "passive"))
      (node (ref "D8") (pin "A") (pinfunction "A_A") (pintype "passive"))
      (node (ref "L4") (pin "1") (pinfunction "1_1") (pintype "passive"))
    )
    (net (code "26") (name "Net-(C32-Pad2)") (class "Default")
      (node (ref "C32") (pin "2") (pinfunction "2_2") (pintype "passive"))
      (node (ref "R19") (pin "2") (pinfunction "2_2") (pintype "passive"))
    )
    (net (code "27") (name "Net-(C34-+)") (class "Default")
      (node (ref "C34") (pin "1") (pinfunction "+_1") (pintype "passive"))
      (node (ref "C37") (pin "1") (pinfunction "1_1") (pintype "passive"))
      (node (ref "C38") (pin "1") (pinfunction "1_1") (pintype "passive"))
      (node (ref "IC5") (pin "11") (pinfunction "OUT_11") (pintype "output"))
      (node (ref "L6") (pin "1") (pinfunction "1_1") (pintype "passive"))
      (node (ref "R20") (pin "1") (pinfunction "1_1") (pintype "passive"))
      (node (ref "TR1") (pin "3") (pinfunction "3_3") (pintype "passive"))
    )
    (net (code "28") (name "Net-(C40-Pad2)") (class "Default")
      (node (ref "C40") (pin "2") (pinfunction "2_2") (pintype "passive"))
      (node (ref "R23") (pin "2") (pinfunction "2_2") (pintype "passive"))
    )
    (net (code "29") (name "Net-(C44-Pad1)") (class "Default")
      (node (ref "C44") (pin "1") (pinfunction "1_1") (pintype "passive"))
      (node (ref "R38") (pin "1") (pinfunction "1_1") (pintype "passive"))
    )
    (net (code "30") (name "Net-(C45-Pad2)") (class "Default")
      (node (ref "C45") (pin "2") (pinfunction "2_2") (pintype "passive"))
      (node (ref "R43") (pin "1") (pinfunction "1_1") (pintype "passive"))
    )
    (net (code "31") (name "Net-(C46-Pad2)") (class "Default")
      (node (ref "C46") (pin "2") (pinfunction "2_2") (pintype "passive"))
      (node (ref "R45") (pin "1") (pinfunction "1_1") (pintype "passive"))
    )
    (net (code "32") (name "Net-(C47-Pad1)") (class "Default")
      (node (ref "C47") (pin "1") (pinfunction "1_1") (pintype "passive"))
      (node (ref "R46") (pin "2") (pinfunction "2_2") (pintype "passive"))
      (node (ref "R47") (pin "1") (pinfunction "1_1") (pintype "passive"))
    )
    (net (code "33") (name "Net-(C48-Pad1)") (class "Default")
      (node (ref "C48") (pin "1") (pinfunction "1_1") (pintype "passive"))
      (node (ref "R56") (pin "2") (pinfunction "2_2") (pintype "passive"))
      (node (ref "R57") (pin "1") (pinfunction "1_1") (pintype "passive"))
    )
    (net (code "34") (name "Net-(C49-Pad2)") (class "Default")
      (node (ref "C49") (pin "2") (pinfunction "2_2") (pintype "passive"))
      (node (ref "R54") (pin "1") (pinfunction "1_1") (pintype "passive"))
    )
    (net (code "35") (name "Net-(C50-Pad2)") (class "Default")
      (node (ref "C50") (pin "2") (pinfunction "2_2") (pintype "passive"))
      (node (ref "R55") (pin "1") (pinfunction "1_1") (pintype "passive"))
    )
    (net (code "36") (name "Net-(C51-Pad2)") (class "Default")
      (node (ref "C51") (pin "2") (pinfunction "2_2") (pintype "passive"))
      (node (ref "R58") (pin "1") (pinfunction "1_1") (pintype "passive"))
    )
    (net (code "37") (name "Net-(C62-Pad1)") (class "Default")
      (node (ref "C62") (pin "1") (pinfunction "1_1") (pintype "passive"))
      (node (ref "R71") (pin "1") (pinfunction "1_1") (pintype "passive"))
    )
    (net (code "38") (name "Net-(C63-Pad2)") (class "Default")
      (node (ref "C63") (pin "2") (pinfunction "2_2") (pintype "passive"))
      (node (ref "R72") (pin "1") (pinfunction "1_1") (pintype "passive"))
    )
    (net (code "39") (name "Net-(D1-C)") (class "Default")
      (node (ref "D1") (pin "3") (pinfunction "C_3") (pintype "passive"))
      (node (ref "D2") (pin "1") (pinfunction "A1_1") (pintype "passive"))
      (node (ref "D2") (pin "2") (pinfunction "A2_2") (pintype "passive"))
      (node (ref "X1") (pin "1") (pinfunction "1_1") (pintype "bidirectional"))
    )
    (net (code "40") (name "Net-(D3-C)") (class "Default")
      (node (ref "D3") (pin "3") (pinfunction "C_3") (pintype "passive"))
      (node (ref "D4") (pin "1") (pinfunction "A1_1") (pintype "passive"))
      (node (ref "D4") (pin "2") (pinfunction "A2_2") (pintype "passive"))
      (node (ref "X1") (pin "2") (pinfunction "1_2") (pintype "bidirectional"))
    )
    (net (code "41") (name "Net-(D6-C)") (class "Default")
      (node (ref "C15") (pin "1") (pinfunction "1_1") (pintype "passive"))
      (node (ref "D6") (pin "3") (pinfunction "C_3") (pintype "passive"))
      (node (ref "L1") (pin "1") (pinfunction "1_1") (pintype "passive"))
      (node (ref "Q1") (pin "2") (pinfunction "D_2") (pintype "passive"))
    )
    (net (code "42") (name "Net-(D7-PadA)") (class "Default")
      (node (ref "D7") (pin "A") (pinfunction "A_A") (pintype "passive"))
      (node (ref "Q2") (pin "B") (pinfunction "B_B") (pintype "passive"))
      (node (ref "R12") (pin "2") (pinfunction "2_2") (pintype "passive"))
      (node (ref "R15") (pin "1") (pinfunction "1_1") (pintype "passive"))
    )
    (net (code "43") (name "Net-(D7-PadC)") (class "Default")
      (node (ref "D7") (pin "C") (pinfunction "C_C") (pintype "passive"))
      (node (ref "Q2") (pin "E") (pinfunction "E_E") (pintype "passive"))
      (node (ref "R11") (pin "2") (pinfunction "2_2") (pintype "passive"))
    )
    (net (code "44") (name "Net-(D8-PadC)") (class "Default")
      (node (ref "D8") (pin "C") (pinfunction "C_C") (pintype "passive"))
      (node (ref "TR1") (pin "2") (pinfunction "2_2") (pintype "passive"))
    )
    (net (code "45") (name "Net-(D12-PadC)") (class "Default")
      (node (ref "D12") (pin "C") (pinfunction "C_C") (pintype "passive"))
      (node (ref "D13") (pin "A") (pinfunction "A_A") (pintype "passive"))
      (node (ref "Q4") (pin "G") (pinfunction "G_G") (pintype "passive"))
      (node (ref "R30") (pin "1") (pinfunction "1_1") (pintype "passive"))
    )
    (net (code "46") (name "Net-(D13-PadC)") (class "Default")
      (node (ref "D13") (pin "C") (pinfunction "C_C") (pintype "passive"))
      (node (ref "ZD3") (pin "C") (pinfunction "C_C") (pintype "passive"))
    )
    (net (code "47") (name "Net-(D14-PadC)") (class "Default")
      (node (ref "D14") (pin "C") (pinfunction "C_C") (pintype "passive"))
      (node (ref "Q9") (pin "2") (pinfunction "C_2") (pintype "passive"))
      (node (ref "Q9") (pin "4") (pinfunction "C_4") (pintype "passive"))
      (node (ref "ZD3") (pin "A") (pinfunction "A_A") (pintype "passive"))
    )
    (net (code "48") (name "Net-(D15-PadC)") (class "Default")
      (node (ref "D15") (pin "C") (pinfunction "C_C") (pintype "passive"))
      (node (ref "Q6") (pin "C") (pinfunction "C_C") (pintype "passive"))
      (node (ref "ZD2") (pin "C") (pinfunction "C_C") (pintype "passive"))
    )
    (net (code "49") (name "Net-(D16-PadA)") (class "Default")
      (node (ref "D16") (pin "A") (pinfunction "A_A") (pintype "passive"))
      (node (ref "D18") (pin "A") (pinfunction "A_A") (pintype "passive"))
      (node (ref "R50") (pin "1") (pinfunction "1_1") (pintype "passive"))
    )
    (net (code "50") (name "Net-(FB-1)") (class "Default")
      (node (ref "C26") (pin "2") (pinfunction "2_2") (pintype "passive"))
      (node (ref "D9") (pin "A") (pinfunction "A_A") (pintype "passive"))
      (node (ref "FB") (pin "P$1") (pinfunction "1_P$1") (pintype "passive"))
      (node (ref "IC3") (pin "1") (pinfunction "OUT_1") (pintype "passive"))
    )
    (net (code "51") (name "Net-(FB2-1)") (class "Default")
      (node (ref "C29") (pin "1") (pinfunction "1_1") (pintype "passive"))
      (node (ref "D10") (pin "C") (pinfunction "C_C") (pintype "passive"))
      (node (ref "FB2") (pin "P$1") (pinfunction "1_P$1") (pintype "passive"))
      (node (ref "IC4") (pin "1") (pinfunction "VO_1") (pintype "passive"))
    )
    (net (code "52") (name "Net-(IC1-CAP)") (class "Default")
      (node (ref "C6") (pin "1") (pinfunction "1_1") (pintype "passive"))
      (node (ref "IC1") (pin "9") (pinfunction "CAP_9") (pintype "passive"))
    )
    (net (code "53") (name "Net-(IC1-FREQ)") (class "Default")
      (node (ref "IC1") (pin "2") (pinfunction "FREQ_2") (pintype "input"))
      (node (ref "R5") (pin "1") (pinfunction "1_1") (pintype "passive"))
    )
    (net (code "54") (name "Net-(IC1-GATE)") (class "Default")
      (node (ref "IC1") (pin "12") (pinfunction "GATE_12") (pintype "output"))
      (node (ref "R7") (pin "2") (pinfunction "2_2") (pintype "passive"))
    )
    (net (code "55") (name "Net-(IC1-ITH)") (class "Default")
      (node (ref "C19") (pin "1") (pinfunction "1_1") (pintype "passive"))
      (node (ref "IC1") (pin "6") (pinfunction "ITH_6") (pintype "bidirectional"))
      (node (ref "R10") (pin "2") (pinfunction "2_2") (pintype "passive"))
    )
    (net (code "56") (name "Net-(IC1-PLLIN{slash}MODE)") (class "Default")
      (node (ref "IC1") (pin "1") (pinfunction "PLLIN/MODE_1") (pintype "input"))
      (node (ref "JMP1") (pin "2") (pinfunction "2_2") (pintype "passive"))
    )
    (net (code "57") (name "Net-(IC1-RUN)") (class "Default")
      (node (ref "IC1") (pin "8") (pinfunction "RUN_8") (pintype "input"))
      (node (ref "R4") (pin "1") (pinfunction "1_1") (pintype "passive"))
    )
    (net (code "58") (name "Net-(IC1-SENSE)") (class "Default")
      (node (ref "C8") (pin "2") (pinfunction "2_2") (pintype "passive"))
      (node (ref "IC1") (pin "10") (pinfunction "SENSE_10") (pintype "input"))
      (node (ref "R3") (pin "2") (pinfunction "2_2") (pintype "passive"))
    )
    (net (code "59") (name "Net-(IC1-SS)") (class "Default")
      (node (ref "C9") (pin "2") (pinfunction "2_2") (pintype "passive"))
      (node (ref "IC1") (pin "4") (pinfunction "SS_4") (pintype "input"))
    )
    (net (code "60") (name "Net-(IC1-VFB)") (class "Default")
      (node (ref "IC1") (pin "5") (pinfunction "VFB_5") (pintype "input"))
      (node (ref "Q3") (pin "2") (pinfunction "S_2") (pintype "passive"))
      (node (ref "R13") (pin "2") (pinfunction "2_2") (pintype "passive"))
      (node (ref "R14") (pin "1") (pinfunction "1_1") (pintype "passive"))
      (node (ref "R16") (pin "1") (pinfunction "1_1") (pintype "passive"))
    )
    (net (code "61") (name "Net-(IC2-B1)") (class "Default")
      (node (ref "IC2") (pin "6") (pinfunction "B1_6") (pintype "output"))
      (node (ref "X2") (pin "3") (pinfunction "1_3") (pintype "passive"))
    )
    (net (code "62") (name "Net-(IC2-GND2)") (class "Default")
      (node (ref "C22") (pin "2") (pinfunction "2_2") (pintype "passive"))
      (node (ref "IC2") (pin "5") (pinfunction "GND2_5") (pintype "power_in"))
      (node (ref "X2") (pin "1") (pinfunction "1_1") (pintype "passive"))
    )
    (net (code "63") (name "Net-(IC2-VDD2)") (class "Default")
      (node (ref "C22") (pin "1") (pinfunction "1_1") (pintype "passive"))
      (node (ref "IC2") (pin "8") (pinfunction "VDD2_8") (pintype "power_in"))
      (node (ref "X2") (pin "5") (pinfunction "1_5") (pintype "passive"))
    )
    (net (code "64") (name "Net-(IC4-VI)") (class "Default")
      (node (ref "C31") (pin "1") (pinfunction "1_1") (pintype "passive"))
      (node (ref "C35") (pin "1") (pinfunction "1_1") (pintype "passive"))
      (node (ref "C41") (pin "1") (pinfunction "1_1") (pintype "passive"))
      (node (ref "IC4") (pin "8") (pinfunction "VI_8") (pintype "input"))
      (node (ref "IC6") (pin "8") (pinfunction "IN_8") (pintype "power_in"))
      (node (ref "L6") (pin "2") (pinfunction "2_2") (pintype "passive"))
      (node (ref "LED1") (pin "A") (pinfunction "A_A") (pintype "passive"))
    )
    (net (code "65") (name "Net-(IC5-BST)") (class "Default")
      (node (ref "C28") (pin "2") (pinfunction "2_2") (pintype "passive"))
      (node (ref "IC5") (pin "16") (pinfunction "BST_16") (pintype "input"))
    )
    (net (code "66") (name "Net-(IC5-COMP)") (class "Default")
      (node (ref "IC5") (pin "5") (pinfunction "COMP_5") (pintype "input"))
      (node (ref "R23") (pin "1") (pinfunction "1_1") (pintype "passive"))
    )
    (net (code "67") (name "Net-(IC5-FB)") (class "Default")
      (node (ref "C40") (pin "1") (pinfunction "1_1") (pintype "passive"))
      (node (ref "IC5") (pin "6") (pinfunction "FB_6") (pintype "input"))
      (node (ref "R20") (pin "2") (pinfunction "2_2") (pintype "passive"))
      (node (ref "R25") (pin "1") (pinfunction "1_1") (pintype "passive"))
    )
    (net (code "68") (name "Net-(IC5-IS)") (class "Default")
      (node (ref "D11") (pin "A") (pinfunction "A_A") (pintype "passive"))
      (node (ref "IC5") (pin "13") (pinfunction "IS_13") (pintype "input"))
      (node (ref "R19") (pin "1") (pinfunction "1_1") (pintype "passive"))
    )
    (net (code "69") (name "Net-(IC5-PRE)") (class "Default")
      (node (ref "C28") (pin "1") (pinfunction "1_1") (pintype "passive"))
      (node (ref "C32") (pin "1") (pinfunction "1_1") (pintype "passive"))
      (node (ref "D11") (pin "C") (pinfunction "C_C") (pintype "passive"))
      (node (ref "IC5") (pin "14") (pinfunction "SW_14") (pintype "output"))
      (node (ref "IC5") (pin "15") (pinfunction "PRE_15") (pintype "input"))
      (node (ref "TR1") (pin "1") (pinfunction "1_1") (pintype "passive"))
    )
    (net (code "70") (name "Net-(IC5-RAMP)") (class "Default")
      (node (ref "C39") (pin "2") (pinfunction "2_2") (pintype "passive"))
      (node (ref "IC5") (pin "8") (pinfunction "RAMP_8") (pintype "input"))
    )
    (net (code "71") (name "Net-(IC5-RT)") (class "Default")
      (node (ref "IC5") (pin "7") (pinfunction "RT_7") (pintype "input"))
      (node (ref "R22") (pin "1") (pinfunction "1_1") (pintype "passive"))
    )
    (net (code "72") (name "Net-(IC5-SD)") (class "Default")
      (node (ref "IC5") (pin "2") (pinfunction "SD_2") (pintype "input"))
      (node (ref "R17") (pin "1") (pinfunction "1_1") (pintype "passive"))
      (node (ref "R18") (pin "2") (pinfunction "2_2") (pintype "passive"))
    )
    (net (code "73") (name "Net-(IC5-SS)") (class "Default")
      (node (ref "C33") (pin "1") (pinfunction "1_1") (pintype "passive"))
      (node (ref "IC5") (pin "10") (pinfunction "SS_10") (pintype "input"))
    )
    (net (code "74") (name "Net-(IC5-VCC)") (class "Default")
      (node (ref "C36") (pin "2") (pinfunction "2_2") (pintype "passive"))
      (node (ref "IC5") (pin "1") (pinfunction "VCC_1") (pintype "power_in"))
    )
    (net (code "75") (name "Net-(IC5-VIN)") (class "Default")
      (node (ref "C30") (pin "1") (pinfunction "1_1") (pintype "passive"))
      (node (ref "IC5") (pin "3") (pinfunction "VIN_3") (pintype "input"))
      (node (ref "L5") (pin "2") (pinfunction "2_2") (pintype "passive"))
      (node (ref "R17") (pin "2") (pinfunction "2_2") (pintype "passive"))
    )
    (net (code "76") (name "Net-(IC6-FB)") (class "Default")
      (node (ref "IC6") (pin "7") (pinfunction "FB_7") (pintype "input"))
      (node (ref "R24") (pin "2") (pinfunction "2_2") (pintype "passive"))
      (node (ref "R26") (pin "1") (pinfunction "1_1") (pintype "passive"))
    )
    (net (code "77") (name "Net-(IC7A-+IN)") (class "Default")
      (node (ref "IC7") (pin "3") (pinfunction "+IN_3") (pintype "input"))
      (node (ref "R45") (pin "2") (pinfunction "2_2") (pintype "passive"))
      (node (ref "R49") (pin "2") (pinfunction "2_2") (pintype "passive"))
    )
    (net (code "78") (name "Net-(IC7A--IN)") (class "Default")
      (node (ref "C49") (pin "1") (pinfunction "1_1") (pintype "passive"))
      (node (ref "D17") (pin "C") (pinfunction "C_C") (pintype "passive"))
      (node (ref "IC7") (pin "2") (pinfunction "-IN_2") (pintype "input"))
      (node (ref "R51") (pin "2") (pinfunction "2_2") (pintype "passive"))
      (node (ref "R55") (pin "2") (pinfunction "2_2") (pintype "passive"))
    )
    (net (code "79") (name "Net-(IC7B-+IN)") (class "Default")
      (node (ref "IC7") (pin "5") (pinfunction "+IN_5") (pintype "input"))
      (node (ref "R42") (pin "2") (pinfunction "2_2") (pintype "passive"))
      (node (ref "R43") (pin "2") (pinfunction "2_2") (pintype "passive"))
      (node (ref "R46") (pin "1") (pinfunction "1_1") (pintype "passive"))
    )
    (net (code "80") (name "Net-(IC7B--IN)") (class "Default")
      (node (ref "IC7") (pin "6") (pinfunction "-IN_6") (pintype "input"))
      (node (ref "R52") (pin "2") (pinfunction "2_2") (pintype "passive"))
      (node (ref "R56") (pin "1") (pinfunction "1_1") (pintype "passive"))
      (node (ref "R58") (pin "2") (pinfunction "2_2") (pintype "passive"))
    )
    (net (code "81") (name "Net-(IC8A-+IN)") (class "Default")
      (node (ref "IC8") (pin "3") (pinfunction "+IN_3") (pintype "input"))
      (node (ref "R62") (pin "2") (pinfunction "2_2") (pintype "passive"))
    )
    (net (code "82") (name "Net-(IC8A--IN)") (class "Default")
      (node (ref "D19") (pin "C") (pinfunction "C_C") (pintype "passive"))
      (node (ref "IC8") (pin "2") (pinfunction "-IN_2") (pintype "input"))
      (node (ref "R65") (pin "2") (pinfunction "2_2") (pintype "passive"))
      (node (ref "R71") (pin "2") (pinfunction "2_2") (pintype "passive"))
      (node (ref "R72") (pin "2") (pinfunction "2_2") (pintype "passive"))
    )
    (net (code "83") (name "Net-(IC8B--IN)") (class "Default")
      (node (ref "IC8") (pin "6") (pinfunction "-IN_6") (pintype "input"))
      (node (ref "IC8") (pin "7") (pinfunction "OUT_7") (pintype "output"))
    )
    (net (code "84") (name "Net-(IC9A-+IN)") (class "Default")
      (node (ref "IC9") (pin "3") (pinfunction "+IN_3") (pintype "input"))
      (node (ref "R61") (pin "2") (pinfunction "2_2") (pintype "passive"))
      (node (ref "R63") (pin "2") (pinfunction "2_2") (pintype "passive"))
    )
    (net (code "85") (name "Net-(IC9A--IN)") (class "Default")
      (node (ref "IC9") (pin "2") (pinfunction "-IN_2") (pintype "input"))
      (node (ref "R67") (pin "2") (pinfunction "2_2") (pintype "passive"))
      (node (ref "R70") (pin "1") (pinfunction "1_1") (pintype "passive"))
    )
    (net (code "86") (name "Net-(IC10-GP0)") (class "Default")
      (node (ref "IC10") (pin "10") (pinfunction "GP0_10") (pintype "bidirectional"))
      (node (ref "JMP2") (pin "1") (pinfunction "1_1") (pintype "passive"))
    )
    (net (code "87") (name "Net-(IC10-INT)") (class "Default")
      (node (ref "IC10") (pin "8") (pinfunction "INT_8") (pintype "output"))
      (node (ref "JMP2") (pin "4") (pinfunction "4_4") (pintype "passive"))
    )
    (net (code "88") (name "Net-(IC12-TRIM{slash}NR)") (class "Default")
      (node (ref "C69") (pin "1") (pinfunction "1_1") (pintype "passive"))
      (node (ref "IC12") (pin "5") (pinfunction "TRIM/NR_5") (pintype "input"))
    )
    (net (code "89") (name "Net-(IC13-AVDD)") (class "Default")
      (node (ref "C72") (pin "2") (pinfunction "2_2") (pintype "passive"))
      (node (ref "C73") (pin "2") (pinfunction "2_2") (pintype "passive"))
      (node (ref "IC13") (pin "12") (pinfunction "AVDD_12") (pintype "power_in"))
      (node (ref "R76") (pin "2") (pinfunction "2_2") (pintype "passive"))
    )
    (net (code "90") (name "Net-(IC14-VD)") (class "Default")
      (node (ref "IC14") (pin "1") (pinfunction "VD_1") (pintype "bidirectional"))
      (node (ref "R78") (pin "1") (pinfunction "1_1") (pintype "passive"))
    )
    (net (code "91") (name "Net-(IC14-VS)") (class "Default")
      (node (ref "IC14") (pin "4") (pinfunction "VS_4") (pintype "bidirectional"))
      (node (ref "IC15") (pin "6") (pinfunction "S1_6") (pintype "bidirectional"))
    )
    (net (code "92") (name "Net-(IC16A-+IN)") (class "Default")
      (node (ref "IC16") (pin "7") (pinfunction "+IN_7") (pintype "input"))
      (node (ref "IC16") (pin "9") (pinfunction "+IN_9") (pintype "input"))
      (node (ref "R81") (pin "1") (pinfunction "1_1") (pintype "passive"))
      (node (ref "R83") (pin "2") (pinfunction "2_2") (pintype "passive"))
    )
    (net (code "93") (name "Net-(IC16A--IN)") (class "Default")
      (node (ref "IC16") (pin "5") (pinfunction "+IN_5") (pintype "input"))
      (node (ref "IC16") (pin "6") (pinfunction "-IN_6") (pintype "input"))
      (node (ref "R79") (pin "2") (pinfunction "2_2") (pintype "passive"))
    )
    (net (code "94") (name "Net-(IC16A-OUT)") (class "Default")
      (node (ref "IC16") (pin "1") (pinfunction "OUT_1") (pintype "open_collector"))
      (node (ref "IC16") (pin "2") (pinfunction "OUT_2") (pintype "open_collector"))
      (node (ref "R82") (pin "1") (pinfunction "1_1") (pintype "passive"))
    )
    (net (code "95") (name "Net-(IC16B--IN)") (class "Default")
      (node (ref "IC16") (pin "10") (pinfunction "-IN_10") (pintype "input"))
      (node (ref "IC16") (pin "4") (pinfunction "-IN_4") (pintype "input"))
      (node (ref "R84") (pin "1") (pinfunction "1_1") (pintype "passive"))
      (node (ref "R86") (pin "2") (pinfunction "2_2") (pintype "passive"))
    )
    (net (code "96") (name "Net-(IC16C--IN)") (class "Default")
      (node (ref "IC16") (pin "11") (pinfunction "+IN_11") (pintype "input"))
      (node (ref "IC16") (pin "8") (pinfunction "-IN_8") (pintype "input"))
      (node (ref "R88") (pin "2") (pinfunction "2_2") (pintype "passive"))
    )
    (net (code "97") (name "Net-(IC16C-OUT)") (class "Default")
      (node (ref "IC16") (pin "13") (pinfunction "OUT_13") (pintype "open_collector"))
      (node (ref "IC16") (pin "14") (pinfunction "OUT_14") (pintype "open_collector"))
      (node (ref "R87") (pin "1") (pinfunction "1_1") (pintype "passive"))
    )
    (net (code "98") (name "Net-(LED1-PadC)") (class "Default")
      (node (ref "LED1") (pin "C") (pinfunction "C_C") (pintype "passive"))
      (node (ref "R21") (pin "1") (pinfunction "1_1") (pintype "passive"))
    )
    (net (code "99") (name "Net-(Q1-G)") (class "Default")
      (node (ref "Q1") (pin "1") (pinfunction "G_1") (pintype "passive"))
      (node (ref "R6") (pin "1") (pinfunction "1_1") (pintype "passive"))
      (node (ref "R7") (pin "1") (pinfunction "1_1") (pintype "passive"))
    )
    (net (code "100") (name "Net-(Q1-S)") (class "Default")
      (node (ref "Q1") (pin "3") (pinfunction "S_3") (pintype "passive"))
      (node (ref "R2") (pin "2") (pinfunction "2_2") (pintype "passive"))
      (node (ref "R3") (pin "1") (pinfunction "1_1") (pintype "passive"))
      (node (ref "R6") (pin "2") (pinfunction "2_2") (pintype "passive"))
    )
    (net (code "101") (name "Net-(Q3-D)") (class "Default")
      (node (ref "Q2") (pin "C") (pinfunction "C_C") (pintype "passive"))
      (node (ref "Q3") (pin "3") (pinfunction "D_3") (pintype "passive"))
    )
    (net (code "102") (name "Net-(Q4-PadS)") (class "Default")
      (node (ref "Q4") (pin "S") (pinfunction "S_S") (pintype "passive"))
      (node (ref "R28") (pin "1") (pinfunction "1_1") (pintype "passive"))
      (node (ref "R28") (pin "1.1") (pinfunction "1_1.1") (pintype "passive"))
      (node (ref "R30") (pin "2") (pinfunction "2_2") (pintype "passive"))
      (node (ref "R31") (pin "2") (pinfunction "2_2") (pintype "passive"))
      (node (ref "R34") (pin "2") (pinfunction "2_2") (pintype "passive"))
      (node (ref "ZD2") (pin "A") (pinfunction "A_A") (pintype "passive"))
    )
    (net (code "103") (name "Net-(Q5-PadB)") (class "Default")
      (node (ref "Q5") (pin "B") (pinfunction "B_B") (pintype "passive"))
      (node (ref "R32") (pin "2") (pinfunction "2_2") (pintype "passive"))
    )
    (net (code "104") (name "Net-(Q6-PadB)") (class "Default")
      (node (ref "Q6") (pin "B") (pinfunction "B_B") (pintype "passive"))
      (node (ref "R31") (pin "1") (pinfunction "1_1") (pintype "passive"))
    )
    (net (code "105") (name "Net-(Q7-B)") (class "Default")
      (node (ref "D15") (pin "A") (pinfunction "A_A") (pintype "passive"))
      (node (ref "Q7") (pin "1") (pinfunction "B_1") (pintype "passive"))
      (node (ref "R38") (pin "2") (pinfunction "2_2") (pintype "passive"))
      (node (ref "R41") (pin "1") (pinfunction "1_1") (pintype "passive"))
    )
    (net (code "106") (name "Net-(Q7-E)") (class "Default")
      (node (ref "D12") (pin "A") (pinfunction "A_A") (pintype "passive"))
      (node (ref "Q7") (pin "3") (pinfunction "E_3") (pintype "passive"))
    )
    (net (code "107") (name "Net-(Q8-G)") (class "Default")
      (node (ref "D14") (pin "A") (pinfunction "A_A") (pintype "passive"))
      (node (ref "Q5") (pin "C") (pinfunction "C_C") (pintype "passive"))
      (node (ref "Q8") (pin "1") (pinfunction "G_1") (pintype "passive"))
      (node (ref "R33") (pin "2") (pinfunction "2_2") (pintype "passive"))
    )
    (net (code "108") (name "Net-(Q8-S)") (class "Default")
      (node (ref "Q8") (pin "3") (pinfunction "S_3") (pintype "passive"))
      (node (ref "R29") (pin "1") (pinfunction "1_1") (pintype "passive"))
      (node (ref "R29") (pin "1.1") (pinfunction "1_1.1") (pintype "passive"))
      (node (ref "R32") (pin "1") (pinfunction "1_1") (pintype "passive"))
      (node (ref "R33") (pin "1") (pinfunction "1_1") (pintype "passive"))
    )
    (net (code "109") (name "Net-(Q9-E)") (class "Default")
      (node (ref "Q9") (pin "3") (pinfunction "E_3") (pintype "passive"))
      (node (ref "R40") (pin "1") (pinfunction "1_1") (pintype "passive"))
    )
    (net (code "110") (name "Net-(Q10-PadB)") (class "Default")
      (node (ref "Q10") (pin "B") (pinfunction "B_B") (pintype "passive"))
      (node (ref "Q10") (pin "C") (pinfunction "C_C") (pintype "passive"))
      (node (ref "Q11") (pin "B") (pinfunction "B_B") (pintype "passive"))
      (node (ref "Q13") (pin "C") (pinfunction "C_C") (pintype "passive"))
    )
    (net (code "111") (name "Net-(Q10-PadE)") (class "Default")
      (node (ref "Q10") (pin "E") (pinfunction "E_E") (pintype "passive"))
      (node (ref "R36") (pin "1") (pinfunction "1_1") (pintype "passive"))
    )
    (net (code "112") (name "Net-(Q11-PadC)") (class "Default")
      (node (ref "Q11") (pin "C") (pinfunction "C_C") (pintype "passive"))
      (node (ref "Q12") (pin "C") (pinfunction "C_C") (pintype "passive"))
      (node (ref "R41") (pin "2") (pinfunction "2_2") (pintype "passive"))
      (node (ref "R48") (pin "2") (pinfunction "2_2") (pintype "passive"))
    )
    (net (code "113") (name "Net-(Q11-PadE)") (class "Default")
      (node (ref "Q11") (pin "E") (pinfunction "E_E") (pintype "passive"))
      (node (ref "R37") (pin "1") (pinfunction "1_1") (pintype "passive"))
    )
    (net (code "114") (name "Net-(Q12-PadB)") (class "Default")
      (node (ref "Q12") (pin "B") (pinfunction "B_B") (pintype "passive"))
      (node (ref "R34") (pin "1") (pinfunction "1_1") (pintype "passive"))
      (node (ref "R44") (pin "2") (pinfunction "2_2") (pintype "passive"))
    )
    (net (code "115") (name "Net-(Q12-PadE)") (class "Default")
      (node (ref "Q12") (pin "E") (pinfunction "E_E") (pintype "passive"))
      (node (ref "R50") (pin "2") (pinfunction "2_2") (pintype "passive"))
    )
    (net (code "116") (name "Net-(Q13-PadE)") (class "Default")
      (node (ref "Q13") (pin "E") (pinfunction "E_E") (pintype "passive"))
      (node (ref "R53") (pin "2") (pinfunction "2_2") (pintype "passive"))
    )
    (net (code "117") (name "Net-(Q14-D)") (class "Default")
      (node (ref "Q14") (pin "3") (pinfunction "D_3") (pintype "passive"))
      (node (ref "R74") (pin "2") (pinfunction "2_2") (pintype "passive"))
    )
    (net (code "118") (name "Net-(R15-Pad2)") (class "Default")
      (node (ref "R15") (pin "2") (pinfunction "2_2") (pintype "passive"))
      (node (ref "ZD1") (pin "C") (pinfunction "C_C") (pintype "passive"))
    )
    (net (code "119") (name "Net-(R60-Pad2)") (class "Default")
      (node (ref "R60") (pin "2") (pinfunction "2_2") (pintype "passive"))
      (node (ref "R61") (pin "1") (pinfunction "1_1") (pintype "passive"))
    )
    (net (code "120") (name "Net-(R63-Pad1)") (class "Default")
      (node (ref "R63") (pin "1") (pinfunction "1_1") (pintype "passive"))
      (node (ref "R64") (pin "2") (pinfunction "2_2") (pintype "passive"))
    )
    (net (code "121") (name "Net-(R67-Pad1)") (class "Default")
      (node (ref "R67") (pin "1") (pinfunction "1_1") (pintype "passive"))
      (node (ref "R68") (pin "2") (pinfunction "2_2") (pintype "passive"))
    )
    (net (code "122") (name "Net-(R69-Pad1)") (class "Default")
      (node (ref "R69") (pin "1") (pinfunction "1_1") (pintype "passive"))
      (node (ref "R70") (pin "2") (pinfunction "2_2") (pintype "passive"))
    )
    (net (code "123") (name "OUT+") (class "Default")
      (node (ref "C47") (pin "2") (pinfunction "2_2") (pintype "passive"))
      (node (ref "C50") (pin "1") (pinfunction "1_1") (pintype "passive"))
      (node (ref "C63") (pin "1") (pinfunction "1_1") (pintype "passive"))
      (node (ref "Q5") (pin "E") (pinfunction "E_E") (pintype "passive"))
      (node (ref "Q6") (pin "E") (pinfunction "E_E") (pintype "passive"))
      (node (ref "R28") (pin "2") (pinfunction "2_2") (pintype "passive"))
      (node (ref "R28") (pin "2.1") (pinfunction "2_2.1") (pintype "passive"))
      (node (ref "R29") (pin "2") (pinfunction "2_2") (pintype "passive"))
      (node (ref "R29") (pin "2.1") (pinfunction "2_2.1") (pintype "passive"))
      (node (ref "R35") (pin "1") (pinfunction "1_1") (pintype "passive"))
      (node (ref "X4") (pin "23") (pinfunction "1_23") (pintype "passive"))
      (node (ref "X4") (pin "24") (pinfunction "1_24") (pintype "passive"))
      (node (ref "X4") (pin "25") (pinfunction "1_25") (pintype "passive"))
      (node (ref "X4") (pin "26") (pinfunction "1_26") (pintype "passive"))
      (node (ref "ZD1") (pin "A") (pinfunction "A_A") (pintype "passive"))
    )
    (net (code "124") (name "OUT-") (class "Default")
      (node (ref "C46") (pin "1") (pinfunction "1_1") (pintype "passive"))
      (node (ref "C48") (pin "2") (pinfunction "2_2") (pintype "passive"))
      (node (ref "R59") (pin "2") (pinfunction "2_2") (pintype "passive"))
      (node (ref "R64") (pin "1") (pinfunction "1_1") (pintype "passive"))
      (node (ref "R66") (pin "1") (pinfunction "1_1") (pintype "passive"))
      (node (ref "X4") (pin "17") (pinfunction "1_17") (pintype "passive"))
      (node (ref "X4") (pin "18") (pinfunction "1_18") (pintype "passive"))
      (node (ref "X4") (pin "19") (pinfunction "1_19") (pintype "passive"))
      (node (ref "X4") (pin "20") (pinfunction "1_20") (pintype "passive"))
    )
    (net (code "125") (name "POST_OE") (class "Default")
      (node (ref "Q15") (pin "3") (pinfunction "D_3") (pintype "passive"))
      (node (ref "R53") (pin "1") (pinfunction "1_1") (pintype "passive"))
    )
    (net (code "126") (name "POUT-") (class "Default")
      (node (ref "C11") (pin "2") (pinfunction "2_2") (pintype "passive"))
      (node (ref "C12") (pin "2") (pinfunction "2_2") (pintype "passive"))
      (node (ref "C13") (pin "2") (pinfunction "2_2") (pintype "passive"))
      (node (ref "C14") (pin "2") (pinfunction "2_2") (pintype "passive"))
      (node (ref "C17") (pin "1") (pinfunction "1_1") (pintype "passive"))
      (node (ref "R66") (pin "2") (pinfunction "2_2") (pintype "passive"))
      (node (ref "R68") (pin "1") (pinfunction "1_1") (pintype "passive"))
      (node (ref "SH1") (pin "P$1") (pinfunction "GND_A_P$1") (pintype "bidirectional"))
    )
    (net (code "127") (name "PREG_OUT") (class "Default")
      (node (ref "FB1") (pin "2") (pinfunction "2_2") (pintype "passive"))
      (node (ref "Q4") (pin "D") (pinfunction "D_D") (pintype "passive"))
    )
    (net (code "128") (name "PRE_OE") (class "Default")
      (node (ref "IC10") (pin "17") (pinfunction "GP7_17") (pintype "bidirectional"))
      (node (ref "OE") (pin "1") (pinfunction "P$1_1") (pintype "bidirectional"))
      (node (ref "Q15") (pin "1") (pinfunction "G_1") (pintype "passive"))
      (node (ref "R4") (pin "2") (pinfunction "2_2") (pintype "passive"))
      (node (ref "R75") (pin "2") (pinfunction "2_2") (pintype "passive"))
    )
    (net (code "129") (name "PS_MISO") (class "Default")
      (node (ref "IC10") (pin "3") (pinfunction "SO_3") (pintype "output"))
      (node (ref "IC13") (pin "15") (pinfunction "DOUT/~{DRDY}_15") (pintype "output"))
      (node (ref "X4") (pin "9") (pinfunction "1_9") (pintype "passive"))
    )
    (net (code "130") (name "PS_MOSI") (class "Default")
      (node (ref "IC10") (pin "2") (pinfunction "SI_2") (pintype "input"))
      (node (ref "IC11") (pin "7") (pinfunction "DIN_7") (pintype "input"))
      (node (ref "IC13") (pin "16") (pinfunction "DIN_16") (pintype "input"))
      (node (ref "X4") (pin "1") (pinfunction "1_1") (pintype "passive"))
    )
    (net (code "131") (name "PS_SCLK") (class "Default")
      (node (ref "IC10") (pin "1") (pinfunction "SCK_1") (pintype "input"))
      (node (ref "IC11") (pin "6") (pinfunction "SCLK_6") (pintype "input"))
      (node (ref "IC13") (pin "1") (pinfunction "SCLK_1") (pintype "input"))
      (node (ref "X4") (pin "7") (pinfunction "1_7") (pintype "passive"))
    )
    (net (code "132") (name "PWRGOOD") (class "Default")
      (node (ref "IC10") (pin "16") (pinfunction "GP6_16") (pintype "bidirectional"))
      (node (ref "IC6") (pin "5") (pinfunction "~{ERROR}_5") (pintype "input"))
      (node (ref "R27") (pin "2") (pinfunction "2_2") (pintype "passive"))
    )
    (net (code "133") (name "SENSE+") (class "Default")
      (node (ref "C45") (pin "1") (pinfunction "1_1") (pintype "passive"))
      (node (ref "R35") (pin "2") (pinfunction "2_2") (pintype "passive"))
      (node (ref "R47") (pin "2") (pinfunction "2_2") (pintype "passive"))
      (node (ref "X4") (pin "22") (pinfunction "1_22") (pintype "passive"))
    )
    (net (code "134") (name "SENSE-") (class "Default")
      (node (ref "C51") (pin "1") (pinfunction "1_1") (pintype "passive"))
      (node (ref "R57") (pin "2") (pinfunction "2_2") (pintype "passive"))
      (node (ref "R59") (pin "1") (pinfunction "1_1") (pintype "passive"))
      (node (ref "X4") (pin "21") (pinfunction "1_21") (pintype "passive"))
    )
    (net (code "135") (name "SGND") (class "Default")
      (node (ref "C19") (pin "2") (pinfunction "2_2") (pintype "passive"))
      (node (ref "C21") (pin "2") (pinfunction "2_2") (pintype "passive"))
      (node (ref "C9") (pin "1") (pinfunction "1_1") (pintype "passive"))
      (node (ref "IC1") (pin "3") (pinfunction "SGND_3") (pintype "passive"))
      (node (ref "JMP1") (pin "1") (pinfunction "1_1") (pintype "passive"))
      (node (ref "R16") (pin "2") (pinfunction "2_2") (pintype "passive"))
      (node (ref "R5") (pin "2") (pinfunction "2_2") (pintype "passive"))
      (node (ref "SH2") (pin "P$1") (pinfunction "GND_A_P$1") (pintype "bidirectional"))
    )
    (net (code "136") (name "SYNC") (class "Default")
      (node (ref "IC2") (pin "2") (pinfunction "A1_2") (pintype "input"))
      (node (ref "IC5") (pin "4") (pinfunction "SYNC_4") (pintype "input"))
      (node (ref "JMP1") (pin "3") (pinfunction "3_3") (pintype "passive"))
      (node (ref "X2") (pin "4") (pinfunction "1_4") (pintype "passive"))
    )
    (net (code "137") (name "TEMP_NTC") (class "Default")
      (node (ref "X3") (pin "1") (pinfunction "1_1") (pintype "passive"))
      (node (ref "X4") (pin "13") (pinfunction "1_13") (pintype "passive"))
    )
    (net (code "138") (name "U_MON") (class "Default")
      (node (ref "IC13") (pin "10") (pinfunction "AIN1_10") (pintype "input"))
      (node (ref "IC7") (pin "7") (pinfunction "OUT_7") (pintype "output"))
      (node (ref "R51") (pin "1") (pinfunction "1_1") (pintype "passive"))
      (node (ref "R52") (pin "1") (pinfunction "1_1") (pintype "passive"))
    )
    (net (code "139") (name "U_SERVO") (class "Default")
      (node (ref "CV") (pin "1") (pinfunction "P$1_1") (pintype "bidirectional"))
      (node (ref "D16") (pin "C") (pinfunction "C_C") (pintype "passive"))
      (node (ref "D17") (pin "A") (pinfunction "A_A") (pintype "passive"))
      (node (ref "IC7") (pin "1") (pinfunction "OUT_1") (pintype "output"))
      (node (ref "R54") (pin "2") (pinfunction "2_2") (pintype "passive"))
      (node (ref "R79") (pin "1") (pinfunction "1_1") (pintype "passive"))
    )
    (net (code "140") (name "U_SET") (class "Default")
      (node (ref "IC15") (pin "5") (pinfunction "D_5") (pintype "bidirectional"))
      (node (ref "R49") (pin "1") (pinfunction "1_1") (pintype "passive"))
      (node (ref "R77") (pin "1") (pinfunction "1_1") (pintype "passive"))
    )
    (net (code "141") (name "U_SET_IN") (class "Default")
      (node (ref "IC11") (pin "4") (pinfunction "VOUTA_4") (pintype "output"))
      (node (ref "IC13") (pin "11") (pinfunction "AIN0/REFP1_11") (pintype "input"))
      (node (ref "X5") (pin "1") (pinfunction "1_1") (pintype "passive"))
    )
    (net (code "142") (name "U_SET_OUT") (class "Default")
      (node (ref "IC15") (pin "4") (pinfunction "S2_4") (pintype "bidirectional"))
      (node (ref "R77") (pin "2") (pinfunction "2_2") (pintype "passive"))
      (node (ref "X5") (pin "3") (pinfunction "1_3") (pintype "passive"))
    )
    (net (code "143") (name "V+") (class "Default")
      (node (ref "C52") (pin "2") (pinfunction "2_2") (pintype "passive"))
      (node (ref "C53") (pin "1") (pinfunction "1_1") (pintype "passive"))
      (node (ref "C54") (pin "2") (pinfunction "2_2") (pintype "passive"))
      (node (ref "C55") (pin "2") (pinfunction "2_2") (pintype "passive"))
      (node (ref "C56") (pin "2") (pinfunction "2_2") (pintype "passive"))
      (node (ref "C75") (pin "2") (pinfunction "2_2") (pintype "passive"))
      (node (ref "FB2") (pin "P$2") (pinfunction "2_P$2") (pintype "passive"))
      (node (ref "IC14") (pin "6") (pinfunction "VDD_6") (pintype "bidirectional"))
      (node (ref "IC15") (pin "2") (pinfunction "VDD_2") (pintype "power_in"))
      (node (ref "IC16") (pin "3") (pinfunction "V+_3") (pintype "power_in"))
      (node (ref "IC7") (pin "8") (pinfunction "V+_8") (pintype "power_in"))
      (node (ref "IC8") (pin "8") (pinfunction "V+_8") (pintype "power_in"))
      (node (ref "IC9") (pin "7") (pinfunction "V+_7") (pintype "power_in"))
      (node (ref "R81") (pin "2") (pinfunction "2_2") (pintype "passive"))
    )
    (net (code "144") (name "V-") (class "Default")
      (node (ref "C57") (pin "2") (pinfunction "2_2") (pintype "passive"))
      (node (ref "C58") (pin "2") (pinfunction "2_2") (pintype "passive"))
      (node (ref "C59") (pin "1") (pinfunction "1_1") (pintype "passive"))
      (node (ref "C60") (pin "2") (pinfunction "2_2") (pintype "passive"))
      (node (ref "C61") (pin "2") (pinfunction "2_2") (pintype "passive"))
      (node (ref "C76") (pin "2") (pinfunction "2_2") (pintype "passive"))
      (node (ref "FB") (pin "P$2") (pinfunction "2_P$2") (pintype "passive"))
      (node (ref "IC14") (pin "3") (pinfunction "VSS_3") (pintype "bidirectional"))
      (node (ref "IC16") (pin "12") (pinfunction "GND_12") (pintype "power_in"))
      (node (ref "IC7") (pin "4") (pinfunction "V-_4") (pintype "power_in"))
      (node (ref "IC8") (pin "4") (pinfunction "V-_4") (pintype "power_in"))
      (node (ref "IC9") (pin "4") (pinfunction "V-_4") (pintype "power_in"))
      (node (ref "R86") (pin "1") (pinfunction "1_1") (pintype "passive"))
    )
    (net (code "145") (name "VBIAS") (class "Default")
      (node (ref "BIAS") (pin "1") (pinfunction "P$1_1") (pintype "bidirectional"))
      (node (ref "C43") (pin "1") (pinfunction "1_1") (pintype "passive"))
      (node (ref "C5") (pin "+") (pinfunction "+_+") (pintype "passive"))
      (node (ref "C5") (pin "+.1") (pinfunction "+_+.1") (pintype "passive"))
      (node (ref "D5") (pin "C") (pinfunction "C_C") (pintype "passive"))
      (node (ref "Q7") (pin "2") (pinfunction "C_2") (pintype "passive"))
      (node (ref "Q7") (pin "4") (pinfunction "C_4") (pintype "passive"))
      (node (ref "R36") (pin "2") (pinfunction "2_2") (pintype "passive"))
      (node (ref "R37") (pin "2") (pinfunction "2_2") (pintype "passive"))
    )
    (net (code "146") (name "unconnected-(IC1-PGOOD-Pad7)") (class "Default")
      (node (ref "IC1") (pin "7") (pinfunction "PGOOD_7") (pintype "output"))
    )
    (net (code "147") (name "unconnected-(IC6-SD-Pad3)") (class "Default")
      (node (ref "IC6") (pin "3") (pinfunction "SD_3") (pintype "input"))
    )
    (net (code "148") (name "unconnected-(IC6-SENSE-Pad2)") (class "Default")
      (node (ref "IC6") (pin "2") (pinfunction "SENSE_2") (pintype "input"))
    )
    (net (code "149") (name "unconnected-(IC6-VTAP-Pad6)") (class "Default")
      (node (ref "IC6") (pin "6") (pinfunction "VTAP_6") (pintype "input"))
    )
    (net (code "150") (name "unconnected-(IC12-TEMP-Pad3)") (class "Default")
      (node (ref "IC12") (pin "3") (pinfunction "TEMP_3") (pintype "input"))
    )
    (net (code "151") (name "~{DP_DRIVE}") (class "Default")
      (node (ref "Q9") (pin "1") (pinfunction "B_1") (pintype "passive"))
      (node (ref "R39") (pin "1") (pinfunction "1_1") (pintype "passive"))
      (node (ref "R74") (pin "1") (pinfunction "1_1") (pintype "passive"))
    )
    (net (code "152") (name "~{INT}") (class "Default")
      (node (ref "JMP2") (pin "3") (pinfunction "3_3") (pintype "passive"))
      (node (ref "X4") (pin "8") (pinfunction "1_8") (pintype "passive"))
    )
    (net (code "153") (name "~{PS_DRDY}") (class "Default")
      (node (ref "IC13") (pin "14") (pinfunction "~{DRDY}_14") (pintype "output"))
      (node (ref "JMP2") (pin "2") (pinfunction "2_2") (pintype "passive"))
    )
    (net (code "154") (name "~{PS_RESET}") (class "Default")
      (node (ref "IC10") (pin "6") (pinfunction "~{RESET}_6") (pintype "input"))
      (node (ref "X4") (pin "5") (pinfunction "1_5") (pintype "passive"))
    )
    (net (code "155") (name "~{SET_100%}") (class "Default")
      (node (ref "IC10") (pin "13") (pinfunction "GP3_13") (pintype "bidirectional"))
      (node (ref "Q3") (pin "1") (pinfunction "G_1") (pintype "passive"))
    )
    (net (code "156") (name "~{SET_DP}") (class "Default")
      (node (ref "IC10") (pin "11") (pinfunction "GP1_11") (pintype "bidirectional"))
      (node (ref "Q14") (pin "1") (pinfunction "G_1") (pintype "passive"))
      (node (ref "R73") (pin "2") (pinfunction "2_2") (pintype "passive"))
    )
  )
)
